# PowerPCB_mk1.net
KiCad netlist of a schematic drawn in EAGLE
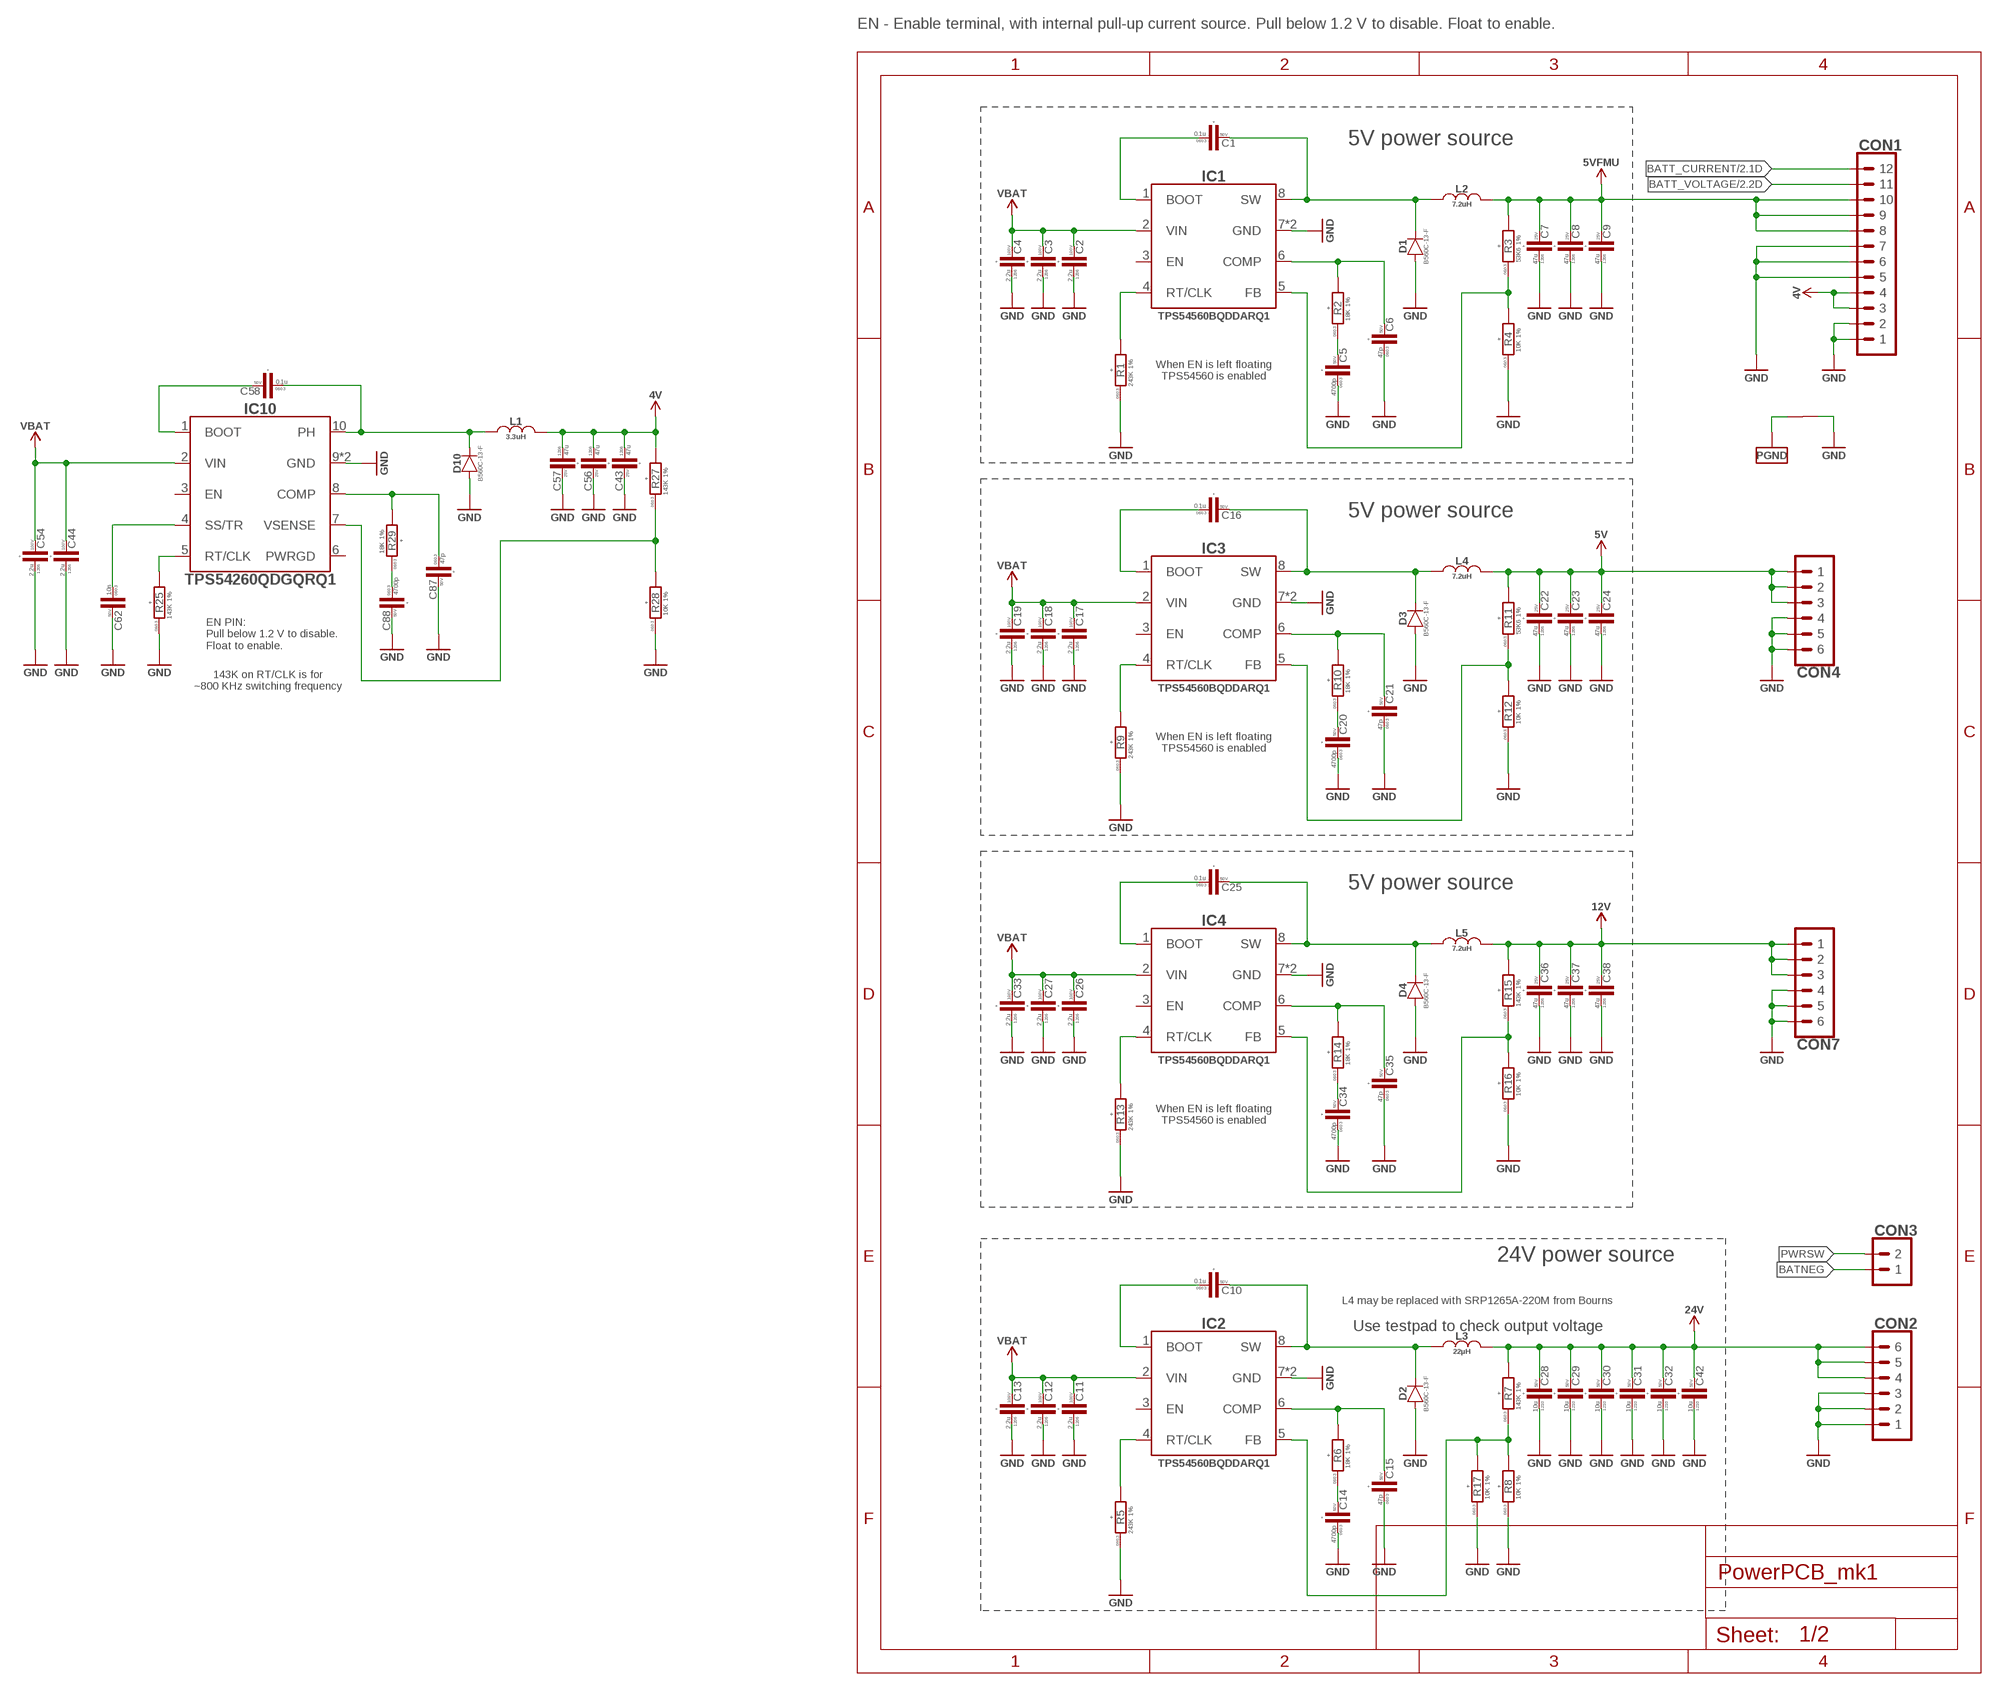
[diagram p0: schematic, sheet 1]
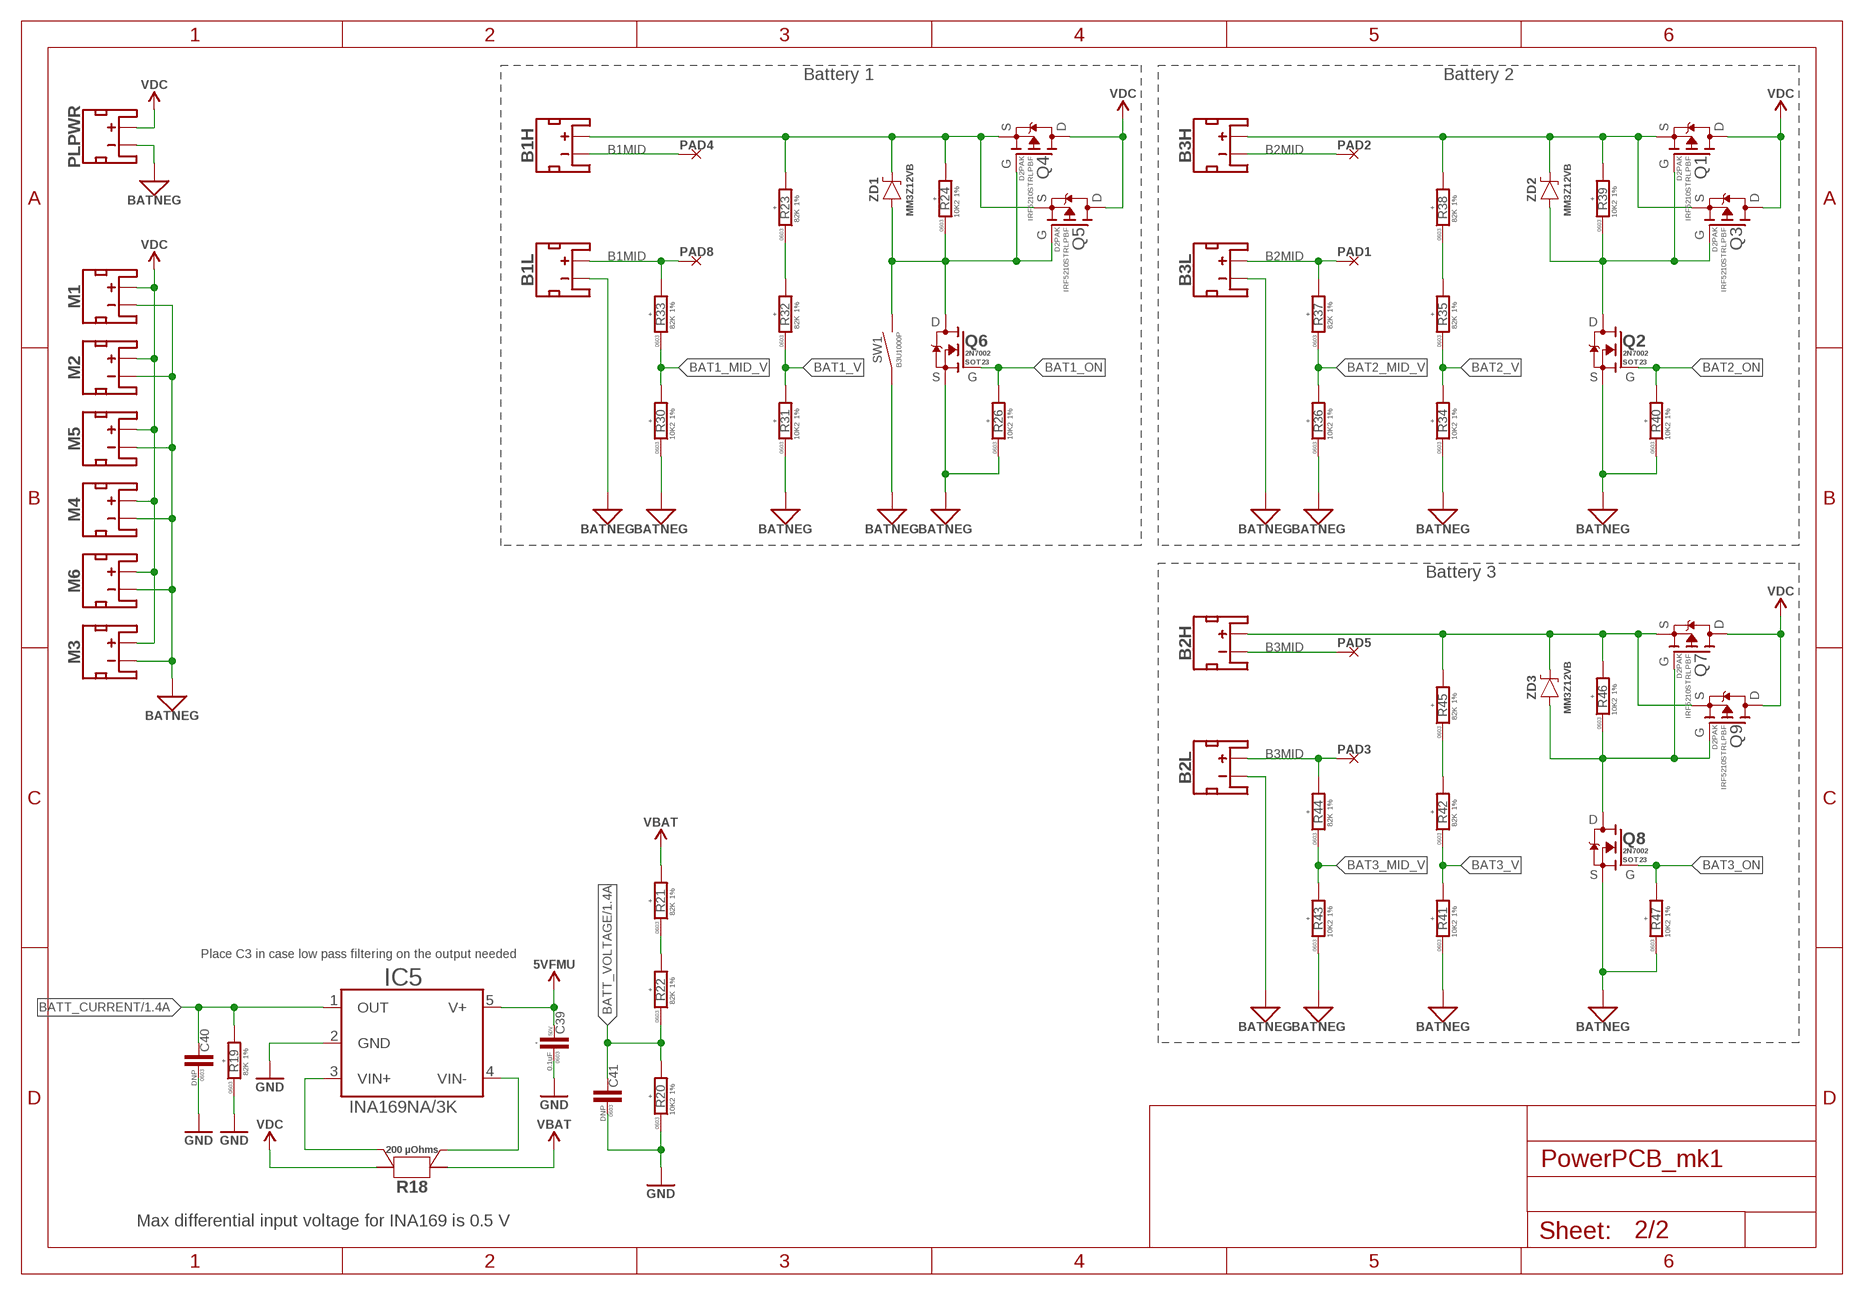
[diagram p1: schematic, sheet 2]

(export (version "E")
  (design (tool "Eeschema 10.0.6"))
  (components
    (comp (ref "B1H")
      (value "BATTERY_CON-XT60PW-M")
      (footprint "eagle-import:XT60PW-M")
      (libsource (lib "eagle-import") (part "BATTERY_CON-XT60PW-M"))
    )
    (comp (ref "B1L")
      (value "BATTERY_CON-XT60PW-M")
      (footprint "eagle-import:XT60PW-M")
      (libsource (lib "eagle-import") (part "BATTERY_CON-XT60PW-M"))
    )
    (comp (ref "B2H")
      (value "BATTERY_CON-XT60PW-M")
      (footprint "eagle-import:XT60PW-M")
      (libsource (lib "eagle-import") (part "BATTERY_CON-XT60PW-M"))
    )
    (comp (ref "B2L")
      (value "BATTERY_CON-XT60PW-M")
      (footprint "eagle-import:XT60PW-M")
      (libsource (lib "eagle-import") (part "BATTERY_CON-XT60PW-M"))
    )
    (comp (ref "B3H")
      (value "BATTERY_CON-XT60PW-M")
      (footprint "eagle-import:XT60PW-M")
      (libsource (lib "eagle-import") (part "BATTERY_CON-XT60PW-M"))
    )
    (comp (ref "B3L")
      (value "BATTERY_CON-XT60PW-M")
      (footprint "eagle-import:XT60PW-M")
      (libsource (lib "eagle-import") (part "BATTERY_CON-XT60PW-M"))
    )
    (comp (ref "C39")
      (value "0.1uF")
      (footprint "eagle-import:C0603")
      (fields
        (field (name "PACKAGE") "0603")
        (field (name "ALLOCATED") "+")
        (field (name "LCSC#") "C14663")
        (field (name "MANF") "YAGEO")
        (field (name "MANF#") "CC0603KRX7R9BB104")
        (field (name "VOLTAGE") "50V")
      )
      (libsource (lib "eagle-import") (part "C-0603"))
    )
    (comp (ref "C40")
      (value "DNP")
      (footprint "eagle-import:C0603")
      (fields (field (name "PACKAGE") "0603"))
      (libsource (lib "eagle-import") (part "C-0603"))
    )
    (comp (ref "C41")
      (value "DNP")
      (footprint "eagle-import:C0603")
      (fields (field (name "PACKAGE") "0603"))
      (libsource (lib "eagle-import") (part "C-0603"))
    )
    (comp (ref "IC5")
      (value "INA169")
      (footprint "eagle-import:SOT23-5")
      (fields (field (name "MANF") "Texas Instruments"))
      (libsource (lib "eagle-import") (part "INA169"))
    )
    (comp (ref "M1")
      (value "BATTERY_CON-XT30-RA")
      (footprint "eagle-import:XT30-RA")
      (fields (field (name "MANF") "AMASS"))
      (libsource (lib "eagle-import") (part "BATTERY_CON-XT30-RA"))
    )
    (comp (ref "M2")
      (value "BATTERY_CON-XT30-RA")
      (footprint "eagle-import:XT30-RA")
      (fields (field (name "MANF") "AMASS"))
      (libsource (lib "eagle-import") (part "BATTERY_CON-XT30-RA"))
    )
    (comp (ref "M3")
      (value "BATTERY_CON-XT30-RA")
      (footprint "eagle-import:XT30-RA")
      (fields (field (name "MANF") "AMASS"))
      (libsource (lib "eagle-import") (part "BATTERY_CON-XT30-RA"))
    )
    (comp (ref "M4")
      (value "BATTERY_CON-XT30-RA")
      (footprint "eagle-import:XT30-RA")
      (fields (field (name "MANF") "AMASS"))
      (libsource (lib "eagle-import") (part "BATTERY_CON-XT30-RA"))
    )
    (comp (ref "M5")
      (value "BATTERY_CON-XT30-RA")
      (footprint "eagle-import:XT30-RA")
      (fields (field (name "MANF") "AMASS"))
      (libsource (lib "eagle-import") (part "BATTERY_CON-XT30-RA"))
    )
    (comp (ref "M6")
      (value "BATTERY_CON-XT30-RA")
      (footprint "eagle-import:XT30-RA")
      (fields (field (name "MANF") "AMASS"))
      (libsource (lib "eagle-import") (part "BATTERY_CON-XT30-RA"))
    )
    (comp (ref "PAD1")
      (value "PAD-10X4")
      (footprint "eagle-import:10X4")
      (libsource (lib "eagle-import") (part "PAD-10X4"))
    )
    (comp (ref "PAD2")
      (value "PAD-10X4")
      (footprint "eagle-import:10X4")
      (libsource (lib "eagle-import") (part "PAD-10X4"))
    )
    (comp (ref "PAD3")
      (value "PAD-10X4")
      (footprint "eagle-import:10X4")
      (libsource (lib "eagle-import") (part "PAD-10X4"))
    )
    (comp (ref "PAD4")
      (value "PAD-10X4")
      (footprint "eagle-import:10X4")
      (libsource (lib "eagle-import") (part "PAD-10X4"))
    )
    (comp (ref "PAD5")
      (value "PAD-10X4")
      (footprint "eagle-import:10X4")
      (libsource (lib "eagle-import") (part "PAD-10X4"))
    )
    (comp (ref "PAD8")
      (value "PAD-10X4")
      (footprint "eagle-import:10X4")
      (libsource (lib "eagle-import") (part "PAD-10X4"))
    )
    (comp (ref "PLPWR")
      (value "BATTERY_CON-XT30-RA")
      (footprint "eagle-import:XT30-RA")
      (fields (field (name "MANF") "AMASS"))
      (libsource (lib "eagle-import") (part "BATTERY_CON-XT30-RA"))
    )
    (comp (ref "Q1")
      (value "IRF5210S")
      (footprint "eagle-import:D2PAK-3")
      (fields
        (field (name "MANF#") "IRF5210STRLPBF")
        (field (name "PACKAGE") "D2PAK")
        (field (name "MANF") "Infineon Technologies")
      )
      (libsource (lib "eagle-import") (part "IRF5210S"))
    )
    (comp (ref "Q2")
      (value "2N7002")
      (footprint "eagle-import:SOT23")
      (fields
        (field (name "MANF#") "2N7002")
        (field (name "PACKAGE") "SOT23")
        (field (name "MANF") "Changjiang Electronics Tech (CJ)")
      )
      (libsource (lib "eagle-import") (part "2N7002"))
    )
    (comp (ref "Q3")
      (value "IRF5210S")
      (footprint "eagle-import:D2PAK-3")
      (fields
        (field (name "MANF#") "IRF5210STRLPBF")
        (field (name "PACKAGE") "D2PAK")
        (field (name "MANF") "Infineon Technologies")
      )
      (libsource (lib "eagle-import") (part "IRF5210S"))
    )
    (comp (ref "Q4")
      (value "IRF5210S")
      (footprint "eagle-import:D2PAK-3")
      (fields
        (field (name "MANF#") "IRF5210STRLPBF")
        (field (name "PACKAGE") "D2PAK")
        (field (name "MANF") "Infineon Technologies")
      )
      (libsource (lib "eagle-import") (part "IRF5210S"))
    )
    (comp (ref "Q5")
      (value "IRF5210S")
      (footprint "eagle-import:D2PAK-3")
      (fields
        (field (name "MANF#") "IRF5210STRLPBF")
        (field (name "PACKAGE") "D2PAK")
        (field (name "MANF") "Infineon Technologies")
      )
      (libsource (lib "eagle-import") (part "IRF5210S"))
    )
    (comp (ref "Q6")
      (value "2N7002")
      (footprint "eagle-import:SOT23")
      (fields
        (field (name "MANF#") "2N7002")
        (field (name "PACKAGE") "SOT23")
        (field (name "MANF") "Changjiang Electronics Tech (CJ)")
      )
      (libsource (lib "eagle-import") (part "2N7002"))
    )
    (comp (ref "Q7")
      (value "IRF5210S")
      (footprint "eagle-import:D2PAK-3")
      (fields
        (field (name "MANF#") "IRF5210STRLPBF")
        (field (name "PACKAGE") "D2PAK")
        (field (name "MANF") "Infineon Technologies")
      )
      (libsource (lib "eagle-import") (part "IRF5210S"))
    )
    (comp (ref "Q8")
      (value "2N7002")
      (footprint "eagle-import:SOT23")
      (fields
        (field (name "MANF#") "2N7002")
        (field (name "PACKAGE") "SOT23")
        (field (name "MANF") "Changjiang Electronics Tech (CJ)")
      )
      (libsource (lib "eagle-import") (part "2N7002"))
    )
    (comp (ref "Q9")
      (value "IRF5210S")
      (footprint "eagle-import:D2PAK-3")
      (fields
        (field (name "MANF#") "IRF5210STRLPBF")
        (field (name "PACKAGE") "D2PAK")
        (field (name "MANF") "Infineon Technologies")
      )
      (libsource (lib "eagle-import") (part "IRF5210S"))
    )
    (comp (ref "R18")
      (value "200 µOhms")
      (footprint "eagle-import:R3920-KELVIN")
      (fields
        (field (name "MANF") "Bourns Inc")
        (field (name "POWER") "12W")
        (field (name "TOLERANCE") "±1%")
      )
      (libsource (lib "eagle-import") (part "CURRENT_SHUNT_KELVIN-3920-KELVIN-0.0002R"))
    )
    (comp (ref "R19")
      (value "82K")
      (footprint "eagle-import:R0603")
      (fields
        (field (name "PACKAGE") "0603")
        (field (name "TOLERANCE") "1%")
        (field (name "ALLOCATED") "+")
        (field (name "LCSC#") "C23254")
        (field (name "MANF") "UNI-ROYAL(Uniroyal Elec)")
        (field (name "MANF#") "0603WAF8202T5E")
      )
      (libsource (lib "eagle-import") (part "R-0603-1%"))
    )
    (comp (ref "R20")
      (value "10K2")
      (footprint "eagle-import:R0603")
      (fields
        (field (name "PACKAGE") "0603")
        (field (name "TOLERANCE") "1%")
        (field (name "ALLOCATED") "+")
        (field (name "LCSC#") "C22772")
        (field (name "MANF") "UNI-ROYAL(Uniroyal Elec)")
        (field (name "MANF#") "0603WAF1022T5E")
      )
      (libsource (lib "eagle-import") (part "R-0603-1%"))
    )
    (comp (ref "R21")
      (value "82K")
      (footprint "eagle-import:R0603")
      (fields
        (field (name "PACKAGE") "0603")
        (field (name "TOLERANCE") "1%")
        (field (name "ALLOCATED") "+")
        (field (name "LCSC#") "C23254")
        (field (name "MANF") "UNI-ROYAL(Uniroyal Elec)")
        (field (name "MANF#") "0603WAF8202T5E")
      )
      (libsource (lib "eagle-import") (part "R-0603-1%"))
    )
    (comp (ref "R22")
      (value "82K")
      (footprint "eagle-import:R0603")
      (fields
        (field (name "PACKAGE") "0603")
        (field (name "TOLERANCE") "1%")
        (field (name "ALLOCATED") "+")
        (field (name "LCSC#") "C23254")
        (field (name "MANF") "UNI-ROYAL(Uniroyal Elec)")
        (field (name "MANF#") "0603WAF8202T5E")
      )
      (libsource (lib "eagle-import") (part "R-0603-1%"))
    )
    (comp (ref "R23")
      (value "82K")
      (footprint "eagle-import:R0603")
      (fields
        (field (name "PACKAGE") "0603")
        (field (name "TOLERANCE") "1%")
        (field (name "ALLOCATED") "+")
        (field (name "LCSC#") "C23254")
        (field (name "MANF") "UNI-ROYAL(Uniroyal Elec)")
        (field (name "MANF#") "0603WAF8202T5E")
      )
      (libsource (lib "eagle-import") (part "R-0603-1%"))
    )
    (comp (ref "R24")
      (value "10K2")
      (footprint "eagle-import:R0603")
      (fields
        (field (name "PACKAGE") "0603")
        (field (name "TOLERANCE") "1%")
        (field (name "ALLOCATED") "+")
        (field (name "LCSC#") "C22772")
        (field (name "MANF") "UNI-ROYAL(Uniroyal Elec)")
        (field (name "MANF#") "0603WAF1022T5E")
      )
      (libsource (lib "eagle-import") (part "R-0603-1%"))
    )
    (comp (ref "R26")
      (value "10K2")
      (footprint "eagle-import:R0603")
      (fields
        (field (name "PACKAGE") "0603")
        (field (name "TOLERANCE") "1%")
        (field (name "ALLOCATED") "+")
        (field (name "LCSC#") "C22772")
        (field (name "MANF") "UNI-ROYAL(Uniroyal Elec)")
        (field (name "MANF#") "0603WAF1022T5E")
      )
      (libsource (lib "eagle-import") (part "R-0603-1%"))
    )
    (comp (ref "R30")
      (value "10K2")
      (footprint "eagle-import:R0603")
      (fields
        (field (name "PACKAGE") "0603")
        (field (name "TOLERANCE") "1%")
        (field (name "ALLOCATED") "+")
        (field (name "LCSC#") "C22772")
        (field (name "MANF") "UNI-ROYAL(Uniroyal Elec)")
        (field (name "MANF#") "0603WAF1022T5E")
      )
      (libsource (lib "eagle-import") (part "R-0603-1%"))
    )
    (comp (ref "R31")
      (value "10K2")
      (footprint "eagle-import:R0603")
      (fields
        (field (name "PACKAGE") "0603")
        (field (name "TOLERANCE") "1%")
        (field (name "ALLOCATED") "+")
        (field (name "LCSC#") "C22772")
        (field (name "MANF") "UNI-ROYAL(Uniroyal Elec)")
        (field (name "MANF#") "0603WAF1022T5E")
      )
      (libsource (lib "eagle-import") (part "R-0603-1%"))
    )
    (comp (ref "R32")
      (value "82K")
      (footprint "eagle-import:R0603")
      (fields
        (field (name "PACKAGE") "0603")
        (field (name "TOLERANCE") "1%")
        (field (name "ALLOCATED") "+")
        (field (name "LCSC#") "C23254")
        (field (name "MANF") "UNI-ROYAL(Uniroyal Elec)")
        (field (name "MANF#") "0603WAF8202T5E")
      )
      (libsource (lib "eagle-import") (part "R-0603-1%"))
    )
    (comp (ref "R33")
      (value "82K")
      (footprint "eagle-import:R0603")
      (fields
        (field (name "PACKAGE") "0603")
        (field (name "TOLERANCE") "1%")
        (field (name "ALLOCATED") "+")
        (field (name "LCSC#") "C23254")
        (field (name "MANF") "UNI-ROYAL(Uniroyal Elec)")
        (field (name "MANF#") "0603WAF8202T5E")
      )
      (libsource (lib "eagle-import") (part "R-0603-1%"))
    )
    (comp (ref "R34")
      (value "10K2")
      (footprint "eagle-import:R0603")
      (fields
        (field (name "PACKAGE") "0603")
        (field (name "TOLERANCE") "1%")
        (field (name "ALLOCATED") "+")
        (field (name "LCSC#") "C22772")
        (field (name "MANF") "UNI-ROYAL(Uniroyal Elec)")
        (field (name "MANF#") "0603WAF1022T5E")
      )
      (libsource (lib "eagle-import") (part "R-0603-1%"))
    )
    (comp (ref "R35")
      (value "82K")
      (footprint "eagle-import:R0603")
      (fields
        (field (name "PACKAGE") "0603")
        (field (name "TOLERANCE") "1%")
        (field (name "ALLOCATED") "+")
        (field (name "LCSC#") "C23254")
        (field (name "MANF") "UNI-ROYAL(Uniroyal Elec)")
        (field (name "MANF#") "0603WAF8202T5E")
      )
      (libsource (lib "eagle-import") (part "R-0603-1%"))
    )
    (comp (ref "R36")
      (value "10K2")
      (footprint "eagle-import:R0603")
      (fields
        (field (name "PACKAGE") "0603")
        (field (name "TOLERANCE") "1%")
        (field (name "ALLOCATED") "+")
        (field (name "LCSC#") "C22772")
        (field (name "MANF") "UNI-ROYAL(Uniroyal Elec)")
        (field (name "MANF#") "0603WAF1022T5E")
      )
      (libsource (lib "eagle-import") (part "R-0603-1%"))
    )
    (comp (ref "R37")
      (value "82K")
      (footprint "eagle-import:R0603")
      (fields
        (field (name "PACKAGE") "0603")
        (field (name "TOLERANCE") "1%")
        (field (name "ALLOCATED") "+")
        (field (name "LCSC#") "C23254")
        (field (name "MANF") "UNI-ROYAL(Uniroyal Elec)")
        (field (name "MANF#") "0603WAF8202T5E")
      )
      (libsource (lib "eagle-import") (part "R-0603-1%"))
    )
    (comp (ref "R38")
      (value "82K")
      (footprint "eagle-import:R0603")
      (fields
        (field (name "PACKAGE") "0603")
        (field (name "TOLERANCE") "1%")
        (field (name "ALLOCATED") "+")
        (field (name "LCSC#") "C23254")
        (field (name "MANF") "UNI-ROYAL(Uniroyal Elec)")
        (field (name "MANF#") "0603WAF8202T5E")
      )
      (libsource (lib "eagle-import") (part "R-0603-1%"))
    )
    (comp (ref "R39")
      (value "10K2")
      (footprint "eagle-import:R0603")
      (fields
        (field (name "PACKAGE") "0603")
        (field (name "TOLERANCE") "1%")
        (field (name "ALLOCATED") "+")
        (field (name "LCSC#") "C22772")
        (field (name "MANF") "UNI-ROYAL(Uniroyal Elec)")
        (field (name "MANF#") "0603WAF1022T5E")
      )
      (libsource (lib "eagle-import") (part "R-0603-1%"))
    )
    (comp (ref "R40")
      (value "10K2")
      (footprint "eagle-import:R0603")
      (fields
        (field (name "PACKAGE") "0603")
        (field (name "TOLERANCE") "1%")
        (field (name "ALLOCATED") "+")
        (field (name "LCSC#") "C22772")
        (field (name "MANF") "UNI-ROYAL(Uniroyal Elec)")
        (field (name "MANF#") "0603WAF1022T5E")
      )
      (libsource (lib "eagle-import") (part "R-0603-1%"))
    )
    (comp (ref "R41")
      (value "10K2")
      (footprint "eagle-import:R0603")
      (fields
        (field (name "PACKAGE") "0603")
        (field (name "TOLERANCE") "1%")
        (field (name "ALLOCATED") "+")
        (field (name "LCSC#") "C22772")
        (field (name "MANF") "UNI-ROYAL(Uniroyal Elec)")
        (field (name "MANF#") "0603WAF1022T5E")
      )
      (libsource (lib "eagle-import") (part "R-0603-1%"))
    )
    (comp (ref "R42")
      (value "82K")
      (footprint "eagle-import:R0603")
      (fields
        (field (name "PACKAGE") "0603")
        (field (name "TOLERANCE") "1%")
        (field (name "ALLOCATED") "+")
        (field (name "LCSC#") "C23254")
        (field (name "MANF") "UNI-ROYAL(Uniroyal Elec)")
        (field (name "MANF#") "0603WAF8202T5E")
      )
      (libsource (lib "eagle-import") (part "R-0603-1%"))
    )
    (comp (ref "R43")
      (value "10K2")
      (footprint "eagle-import:R0603")
      (fields
        (field (name "PACKAGE") "0603")
        (field (name "TOLERANCE") "1%")
        (field (name "ALLOCATED") "+")
        (field (name "LCSC#") "C22772")
        (field (name "MANF") "UNI-ROYAL(Uniroyal Elec)")
        (field (name "MANF#") "0603WAF1022T5E")
      )
      (libsource (lib "eagle-import") (part "R-0603-1%"))
    )
    (comp (ref "R44")
      (value "82K")
      (footprint "eagle-import:R0603")
      (fields
        (field (name "PACKAGE") "0603")
        (field (name "TOLERANCE") "1%")
        (field (name "ALLOCATED") "+")
        (field (name "LCSC#") "C23254")
        (field (name "MANF") "UNI-ROYAL(Uniroyal Elec)")
        (field (name "MANF#") "0603WAF8202T5E")
      )
      (libsource (lib "eagle-import") (part "R-0603-1%"))
    )
    (comp (ref "R45")
      (value "82K")
      (footprint "eagle-import:R0603")
      (fields
        (field (name "PACKAGE") "0603")
        (field (name "TOLERANCE") "1%")
        (field (name "ALLOCATED") "+")
        (field (name "LCSC#") "C23254")
        (field (name "MANF") "UNI-ROYAL(Uniroyal Elec)")
        (field (name "MANF#") "0603WAF8202T5E")
      )
      (libsource (lib "eagle-import") (part "R-0603-1%"))
    )
    (comp (ref "R46")
      (value "10K2")
      (footprint "eagle-import:R0603")
      (fields
        (field (name "PACKAGE") "0603")
        (field (name "TOLERANCE") "1%")
        (field (name "ALLOCATED") "+")
        (field (name "LCSC#") "C22772")
        (field (name "MANF") "UNI-ROYAL(Uniroyal Elec)")
        (field (name "MANF#") "0603WAF1022T5E")
      )
      (libsource (lib "eagle-import") (part "R-0603-1%"))
    )
    (comp (ref "R47")
      (value "10K2")
      (footprint "eagle-import:R0603")
      (fields
        (field (name "PACKAGE") "0603")
        (field (name "TOLERANCE") "1%")
        (field (name "ALLOCATED") "+")
        (field (name "LCSC#") "C22772")
        (field (name "MANF") "UNI-ROYAL(Uniroyal Elec)")
        (field (name "MANF#") "0603WAF1022T5E")
      )
      (libsource (lib "eagle-import") (part "R-0603-1%"))
    )
    (comp (ref "SW1")
      (value "TACT_SWITCH-B3U1000P")
      (footprint "eagle-import:B3U1000P")
      (fields (field (name "MANF") "OMRON"))
      (libsource (lib "eagle-import") (part "TACT_SWITCH-B3U1000P"))
    )
    (comp (ref "ZD1")
      (value "MM3Z12V")
      (footprint "eagle-import:SOD323")
      (fields (field (name "MANF") "onsemi") (field (name "MANF#") "MM3Z12VB"))
      (libsource (lib "eagle-import") (part "MM3Z12V"))
    )
    (comp (ref "ZD2")
      (value "MM3Z12V")
      (footprint "eagle-import:SOD323")
      (fields (field (name "MANF") "onsemi") (field (name "MANF#") "MM3Z12VB"))
      (libsource (lib "eagle-import") (part "MM3Z12V"))
    )
    (comp (ref "ZD3")
      (value "MM3Z12V")
      (footprint "eagle-import:SOD323")
      (fields (field (name "MANF") "onsemi") (field (name "MANF#") "MM3Z12VB"))
      (libsource (lib "eagle-import") (part "MM3Z12V"))
    )
    (comp (ref "C1")
      (value "0.1u")
      (footprint "eagle-import:C0603")
      (fields
        (field (name "PACKAGE") "0603")
        (field (name "ALLOCATED") "+")
        (field (name "LCSC#") "C14663")
        (field (name "MANF") "YAGEO")
        (field (name "MANF#") "CC0603KRX7R9BB104")
        (field (name "VOLTAGE") "50V")
      )
      (libsource (lib "eagle-import") (part "C-0603"))
    )
    (comp (ref "C2")
      (value "2.2u")
      (footprint "eagle-import:C1206")
      (fields
        (field (name "PACKAGE") "1206")
        (field (name "ALLOCATED") "+")
        (field (name "LCSC#") "C170101")
        (field (name "MANF") "Samsung Electro-Mechanics")
        (field (name "MANF#") "CL31B225KCHSNNE")
        (field (name "VOLTAGE") "100V")
      )
      (libsource (lib "eagle-import") (part "C-1206"))
    )
    (comp (ref "C3")
      (value "2.2u")
      (footprint "eagle-import:C1206")
      (fields
        (field (name "PACKAGE") "1206")
        (field (name "ALLOCATED") "+")
        (field (name "LCSC#") "C170101")
        (field (name "MANF") "Samsung Electro-Mechanics")
        (field (name "MANF#") "CL31B225KCHSNNE")
        (field (name "VOLTAGE") "100V")
      )
      (libsource (lib "eagle-import") (part "C-1206"))
    )
    (comp (ref "C4")
      (value "2.2u")
      (footprint "eagle-import:C1206")
      (fields
        (field (name "PACKAGE") "1206")
        (field (name "ALLOCATED") "+")
        (field (name "LCSC#") "C170101")
        (field (name "MANF") "Samsung Electro-Mechanics")
        (field (name "MANF#") "CL31B225KCHSNNE")
        (field (name "VOLTAGE") "100V")
      )
      (libsource (lib "eagle-import") (part "C-1206"))
    )
    (comp (ref "C5")
      (value "4700p")
      (footprint "eagle-import:C0603")
      (fields
        (field (name "PACKAGE") "0603")
        (field (name "ALLOCATED") "+")
        (field (name "LCSC#") "C106218")
        (field (name "MANF") "YAGEO")
        (field (name "MANF#") "CC0603KRX7R9BB472")
        (field (name "VOLTAGE") "50V")
      )
      (libsource (lib "eagle-import") (part "C-0603"))
    )
    (comp (ref "C6")
      (value "47p")
      (footprint "eagle-import:C0603")
      (fields
        (field (name "PACKAGE") "0603")
        (field (name "ALLOCATED") "+")
        (field (name "LCSC#") "C1671")
        (field (name "MANF") "Samsung Electro-Mechanics")
        (field (name "MANF#") "CL10C470JB8NNNC")
        (field (name "VOLTAGE") "50V")
      )
      (libsource (lib "eagle-import") (part "C-0603"))
    )
    (comp (ref "C7")
      (value "47u")
      (footprint "eagle-import:C1206")
      (fields
        (field (name "PACKAGE") "1206")
        (field (name "ALLOCATED") "+")
        (field (name "LCSC#") "C403725")
        (field (name "MANF") "Murata Electronics")
        (field (name "MANF#") "GRM31CR61E476ME44L")
        (field (name "VOLTAGE") "25V")
      )
      (libsource (lib "eagle-import") (part "C-1206"))
    )
    (comp (ref "C8")
      (value "47u")
      (footprint "eagle-import:C1206")
      (fields
        (field (name "PACKAGE") "1206")
        (field (name "ALLOCATED") "+")
        (field (name "LCSC#") "C403725")
        (field (name "MANF") "Murata Electronics")
        (field (name "MANF#") "GRM31CR61E476ME44L")
        (field (name "VOLTAGE") "25V")
      )
      (libsource (lib "eagle-import") (part "C-1206"))
    )
    (comp (ref "C9")
      (value "47u")
      (footprint "eagle-import:C1206")
      (fields
        (field (name "PACKAGE") "1206")
        (field (name "ALLOCATED") "+")
        (field (name "LCSC#") "C403725")
        (field (name "MANF") "Murata Electronics")
        (field (name "MANF#") "GRM31CR61E476ME44L")
        (field (name "VOLTAGE") "25V")
      )
      (libsource (lib "eagle-import") (part "C-1206"))
    )
    (comp (ref "C10")
      (value "0.1u")
      (footprint "eagle-import:C0603")
      (fields
        (field (name "PACKAGE") "0603")
        (field (name "ALLOCATED") "+")
        (field (name "LCSC#") "C14663")
        (field (name "MANF") "YAGEO")
        (field (name "MANF#") "CC0603KRX7R9BB104")
        (field (name "VOLTAGE") "50V")
      )
      (libsource (lib "eagle-import") (part "C-0603"))
    )
    (comp (ref "C11")
      (value "2.2u")
      (footprint "eagle-import:C1206")
      (fields
        (field (name "PACKAGE") "1206")
        (field (name "ALLOCATED") "+")
        (field (name "LCSC#") "C170101")
        (field (name "MANF") "Samsung Electro-Mechanics")
        (field (name "MANF#") "CL31B225KCHSNNE")
        (field (name "VOLTAGE") "100V")
      )
      (libsource (lib "eagle-import") (part "C-1206"))
    )
    (comp (ref "C12")
      (value "2.2u")
      (footprint "eagle-import:C1206")
      (fields
        (field (name "PACKAGE") "1206")
        (field (name "ALLOCATED") "+")
        (field (name "LCSC#") "C170101")
        (field (name "MANF") "Samsung Electro-Mechanics")
        (field (name "MANF#") "CL31B225KCHSNNE")
        (field (name "VOLTAGE") "100V")
      )
      (libsource (lib "eagle-import") (part "C-1206"))
    )
    (comp (ref "C13")
      (value "2.2u")
      (footprint "eagle-import:C1206")
      (fields
        (field (name "PACKAGE") "1206")
        (field (name "ALLOCATED") "+")
        (field (name "LCSC#") "C170101")
        (field (name "MANF") "Samsung Electro-Mechanics")
        (field (name "MANF#") "CL31B225KCHSNNE")
        (field (name "VOLTAGE") "100V")
      )
      (libsource (lib "eagle-import") (part "C-1206"))
    )
    (comp (ref "C14")
      (value "4700p")
      (footprint "eagle-import:C0603")
      (fields
        (field (name "PACKAGE") "0603")
        (field (name "ALLOCATED") "+")
        (field (name "LCSC#") "C106218")
        (field (name "MANF") "YAGEO")
        (field (name "MANF#") "CC0603KRX7R9BB472")
        (field (name "VOLTAGE") "50V")
      )
      (libsource (lib "eagle-import") (part "C-0603"))
    )
    (comp (ref "C15")
      (value "47p")
      (footprint "eagle-import:C0603")
      (fields
        (field (name "PACKAGE") "0603")
        (field (name "ALLOCATED") "+")
        (field (name "LCSC#") "C1671")
        (field (name "MANF") "Samsung Electro-Mechanics")
        (field (name "MANF#") "CL10C470JB8NNNC")
        (field (name "VOLTAGE") "50V")
      )
      (libsource (lib "eagle-import") (part "C-0603"))
    )
    (comp (ref "C16")
      (value "0.1u")
      (footprint "eagle-import:C0603")
      (fields
        (field (name "PACKAGE") "0603")
        (field (name "ALLOCATED") "+")
        (field (name "LCSC#") "C14663")
        (field (name "MANF") "YAGEO")
        (field (name "MANF#") "CC0603KRX7R9BB104")
        (field (name "VOLTAGE") "50V")
      )
      (libsource (lib "eagle-import") (part "C-0603"))
    )
    (comp (ref "C17")
      (value "2.2u")
      (footprint "eagle-import:C1206")
      (fields
        (field (name "PACKAGE") "1206")
        (field (name "ALLOCATED") "+")
        (field (name "LCSC#") "C170101")
        (field (name "MANF") "Samsung Electro-Mechanics")
        (field (name "MANF#") "CL31B225KCHSNNE")
        (field (name "VOLTAGE") "100V")
      )
      (libsource (lib "eagle-import") (part "C-1206"))
    )
    (comp (ref "C18")
      (value "2.2u")
      (footprint "eagle-import:C1206")
      (fields
        (field (name "PACKAGE") "1206")
        (field (name "ALLOCATED") "+")
        (field (name "LCSC#") "C170101")
        (field (name "MANF") "Samsung Electro-Mechanics")
        (field (name "MANF#") "CL31B225KCHSNNE")
        (field (name "VOLTAGE") "100V")
      )
      (libsource (lib "eagle-import") (part "C-1206"))
    )
    (comp (ref "C19")
      (value "2.2u")
      (footprint "eagle-import:C1206")
      (fields
        (field (name "PACKAGE") "1206")
        (field (name "ALLOCATED") "+")
        (field (name "LCSC#") "C170101")
        (field (name "MANF") "Samsung Electro-Mechanics")
        (field (name "MANF#") "CL31B225KCHSNNE")
        (field (name "VOLTAGE") "100V")
      )
      (libsource (lib "eagle-import") (part "C-1206"))
    )
    (comp (ref "C20")
      (value "4700p")
      (footprint "eagle-import:C0603")
      (fields
        (field (name "PACKAGE") "0603")
        (field (name "ALLOCATED") "+")
        (field (name "LCSC#") "C106218")
        (field (name "MANF") "YAGEO")
        (field (name "MANF#") "CC0603KRX7R9BB472")
        (field (name "VOLTAGE") "50V")
      )
      (libsource (lib "eagle-import") (part "C-0603"))
    )
    (comp (ref "C21")
      (value "47p")
      (footprint "eagle-import:C0603")
      (fields
        (field (name "PACKAGE") "0603")
        (field (name "ALLOCATED") "+")
        (field (name "LCSC#") "C1671")
        (field (name "MANF") "Samsung Electro-Mechanics")
        (field (name "MANF#") "CL10C470JB8NNNC")
        (field (name "VOLTAGE") "50V")
      )
      (libsource (lib "eagle-import") (part "C-0603"))
    )
    (comp (ref "C22")
      (value "47u")
      (footprint "eagle-import:C1206")
      (fields
        (field (name "PACKAGE") "1206")
        (field (name "ALLOCATED") "+")
        (field (name "LCSC#") "C403725")
        (field (name "MANF") "Murata Electronics")
        (field (name "MANF#") "GRM31CR61E476ME44L")
        (field (name "VOLTAGE") "25V")
      )
      (libsource (lib "eagle-import") (part "C-1206"))
    )
    (comp (ref "C23")
      (value "47u")
      (footprint "eagle-import:C1206")
      (fields
        (field (name "PACKAGE") "1206")
        (field (name "ALLOCATED") "+")
        (field (name "LCSC#") "C403725")
        (field (name "MANF") "Murata Electronics")
        (field (name "MANF#") "GRM31CR61E476ME44L")
        (field (name "VOLTAGE") "25V")
      )
      (libsource (lib "eagle-import") (part "C-1206"))
    )
    (comp (ref "C24")
      (value "47u")
      (footprint "eagle-import:C1206")
      (fields
        (field (name "PACKAGE") "1206")
        (field (name "ALLOCATED") "+")
        (field (name "LCSC#") "C403725")
        (field (name "MANF") "Murata Electronics")
        (field (name "MANF#") "GRM31CR61E476ME44L")
        (field (name "VOLTAGE") "25V")
      )
      (libsource (lib "eagle-import") (part "C-1206"))
    )
    (comp (ref "C25")
      (value "0.1u")
      (footprint "eagle-import:C0603")
      (fields
        (field (name "PACKAGE") "0603")
        (field (name "ALLOCATED") "+")
        (field (name "LCSC#") "C14663")
        (field (name "MANF") "YAGEO")
        (field (name "MANF#") "CC0603KRX7R9BB104")
        (field (name "VOLTAGE") "50V")
      )
      (libsource (lib "eagle-import") (part "C-0603"))
    )
    (comp (ref "C26")
      (value "2.2u")
      (footprint "eagle-import:C1206")
      (fields
        (field (name "PACKAGE") "1206")
        (field (name "ALLOCATED") "+")
        (field (name "LCSC#") "C170101")
        (field (name "MANF") "Samsung Electro-Mechanics")
        (field (name "MANF#") "CL31B225KCHSNNE")
        (field (name "VOLTAGE") "100V")
      )
      (libsource (lib "eagle-import") (part "C-1206"))
    )
    (comp (ref "C27")
      (value "2.2u")
      (footprint "eagle-import:C1206")
      (fields
        (field (name "PACKAGE") "1206")
        (field (name "ALLOCATED") "+")
        (field (name "LCSC#") "C170101")
        (field (name "MANF") "Samsung Electro-Mechanics")
        (field (name "MANF#") "CL31B225KCHSNNE")
        (field (name "VOLTAGE") "100V")
      )
      (libsource (lib "eagle-import") (part "C-1206"))
    )
    (comp (ref "C28")
      (value "10u")
      (footprint "eagle-import:C1210")
      (fields
        (field (name "PACKAGE") "1210")
        (field (name "ALLOCATED") "+")
        (field (name "LCSC#") "C77102")
        (field (name "MANF") "Murata Electronics")
        (field (name "MANF#") "GRM32ER71H106K")
        (field (name "VOLTAGE") "50V")
      )
      (libsource (lib "eagle-import") (part "C-1210"))
    )
    (comp (ref "C29")
      (value "10u")
      (footprint "eagle-import:C1210")
      (fields
        (field (name "PACKAGE") "1210")
        (field (name "ALLOCATED") "+")
        (field (name "LCSC#") "C77102")
        (field (name "MANF") "Murata Electronics")
        (field (name "MANF#") "GRM32ER71H106K")
        (field (name "VOLTAGE") "50V")
      )
      (libsource (lib "eagle-import") (part "C-1210"))
    )
    (comp (ref "C30")
      (value "10u")
      (footprint "eagle-import:C1210")
      (fields
        (field (name "PACKAGE") "1210")
        (field (name "ALLOCATED") "+")
        (field (name "LCSC#") "C77102")
        (field (name "MANF") "Murata Electronics")
        (field (name "MANF#") "GRM32ER71H106K")
        (field (name "VOLTAGE") "50V")
      )
      (libsource (lib "eagle-import") (part "C-1210"))
    )
    (comp (ref "C31")
      (value "10u")
      (footprint "eagle-import:C1210")
      (fields
        (field (name "PACKAGE") "1210")
        (field (name "ALLOCATED") "+")
        (field (name "LCSC#") "C77102")
        (field (name "MANF") "Murata Electronics")
        (field (name "MANF#") "GRM32ER71H106K")
        (field (name "VOLTAGE") "50V")
      )
      (libsource (lib "eagle-import") (part "C-1210"))
    )
    (comp (ref "C32")
      (value "10u")
      (footprint "eagle-import:C1210")
      (fields
        (field (name "PACKAGE") "1210")
        (field (name "ALLOCATED") "+")
        (field (name "LCSC#") "C77102")
        (field (name "MANF") "Murata Electronics")
        (field (name "MANF#") "GRM32ER71H106K")
        (field (name "VOLTAGE") "50V")
      )
      (libsource (lib "eagle-import") (part "C-1210"))
    )
    (comp (ref "C33")
      (value "2.2u")
      (footprint "eagle-import:C1206")
      (fields
        (field (name "PACKAGE") "1206")
        (field (name "ALLOCATED") "+")
        (field (name "LCSC#") "C170101")
        (field (name "MANF") "Samsung Electro-Mechanics")
        (field (name "MANF#") "CL31B225KCHSNNE")
        (field (name "VOLTAGE") "100V")
      )
      (libsource (lib "eagle-import") (part "C-1206"))
    )
    (comp (ref "C34")
      (value "4700p")
      (footprint "eagle-import:C0603")
      (fields
        (field (name "PACKAGE") "0603")
        (field (name "ALLOCATED") "+")
        (field (name "LCSC#") "C106218")
        (field (name "MANF") "YAGEO")
        (field (name "MANF#") "CC0603KRX7R9BB472")
        (field (name "VOLTAGE") "50V")
      )
      (libsource (lib "eagle-import") (part "C-0603"))
    )
    (comp (ref "C35")
      (value "47p")
      (footprint "eagle-import:C0603")
      (fields
        (field (name "PACKAGE") "0603")
        (field (name "ALLOCATED") "+")
        (field (name "LCSC#") "C1671")
        (field (name "MANF") "Samsung Electro-Mechanics")
        (field (name "MANF#") "CL10C470JB8NNNC")
        (field (name "VOLTAGE") "50V")
      )
      (libsource (lib "eagle-import") (part "C-0603"))
    )
    (comp (ref "C36")
      (value "47u")
      (footprint "eagle-import:C1206")
      (fields
        (field (name "PACKAGE") "1206")
        (field (name "ALLOCATED") "+")
        (field (name "LCSC#") "C403725")
        (field (name "MANF") "Murata Electronics")
        (field (name "MANF#") "GRM31CR61E476ME44L")
        (field (name "VOLTAGE") "25V")
      )
      (libsource (lib "eagle-import") (part "C-1206"))
    )
    (comp (ref "C37")
      (value "47u")
      (footprint "eagle-import:C1206")
      (fields
        (field (name "PACKAGE") "1206")
        (field (name "ALLOCATED") "+")
        (field (name "LCSC#") "C403725")
        (field (name "MANF") "Murata Electronics")
        (field (name "MANF#") "GRM31CR61E476ME44L")
        (field (name "VOLTAGE") "25V")
      )
      (libsource (lib "eagle-import") (part "C-1206"))
    )
    (comp (ref "C38")
      (value "47u")
      (footprint "eagle-import:C1206")
      (fields
        (field (name "PACKAGE") "1206")
        (field (name "ALLOCATED") "+")
        (field (name "LCSC#") "C403725")
        (field (name "MANF") "Murata Electronics")
        (field (name "MANF#") "GRM31CR61E476ME44L")
        (field (name "VOLTAGE") "25V")
      )
      (libsource (lib "eagle-import") (part "C-1206"))
    )
    (comp (ref "C42")
      (value "10u")
      (footprint "eagle-import:C1210")
      (fields
        (field (name "PACKAGE") "1210")
        (field (name "ALLOCATED") "+")
        (field (name "LCSC#") "C77102")
        (field (name "MANF") "Murata Electronics")
        (field (name "MANF#") "GRM32ER71H106K")
        (field (name "VOLTAGE") "50V")
      )
      (libsource (lib "eagle-import") (part "C-1210"))
    )
    (comp (ref "C43")
      (value "47u")
      (footprint "eagle-import:C1206")
      (fields
        (field (name "PACKAGE") "1206")
        (field (name "ALLOCATED") "+")
        (field (name "LCSC#") "C403725")
        (field (name "MANF") "Murata Electronics")
        (field (name "MANF#") "GRM31CR61E476ME44L")
        (field (name "VOLTAGE") "25V")
      )
      (libsource (lib "eagle-import") (part "C-1206"))
    )
    (comp (ref "C44")
      (value "2.2u")
      (footprint "eagle-import:C1206")
      (fields
        (field (name "PACKAGE") "1206")
        (field (name "ALLOCATED") "+")
        (field (name "LCSC#") "C170101")
        (field (name "MANF") "Samsung Electro-Mechanics")
        (field (name "MANF#") "CL31B225KCHSNNE")
        (field (name "VOLTAGE") "100V")
      )
      (libsource (lib "eagle-import") (part "C-1206"))
    )
    (comp (ref "C54")
      (value "2.2u")
      (footprint "eagle-import:C1206")
      (fields
        (field (name "PACKAGE") "1206")
        (field (name "ALLOCATED") "+")
        (field (name "LCSC#") "C170101")
        (field (name "MANF") "Samsung Electro-Mechanics")
        (field (name "MANF#") "CL31B225KCHSNNE")
        (field (name "VOLTAGE") "100V")
      )
      (libsource (lib "eagle-import") (part "C-1206"))
    )
    (comp (ref "C56")
      (value "47u")
      (footprint "eagle-import:C1206")
      (fields
        (field (name "PACKAGE") "1206")
        (field (name "ALLOCATED") "+")
        (field (name "LCSC#") "C403725")
        (field (name "MANF") "Murata Electronics")
        (field (name "MANF#") "GRM31CR61E476ME44L")
        (field (name "VOLTAGE") "25V")
      )
      (libsource (lib "eagle-import") (part "C-1206"))
    )
    (comp (ref "C57")
      (value "47u")
      (footprint "eagle-import:C1206")
      (fields
        (field (name "PACKAGE") "1206")
        (field (name "ALLOCATED") "+")
        (field (name "LCSC#") "C403725")
        (field (name "MANF") "Murata Electronics")
        (field (name "MANF#") "GRM31CR61E476ME44L")
        (field (name "VOLTAGE") "25V")
      )
      (libsource (lib "eagle-import") (part "C-1206"))
    )
    (comp (ref "C58")
      (value "0.1u")
      (footprint "eagle-import:C0603")
      (fields
        (field (name "PACKAGE") "0603")
        (field (name "ALLOCATED") "+")
        (field (name "LCSC#") "C14663")
        (field (name "MANF") "YAGEO")
        (field (name "MANF#") "CC0603KRX7R9BB104")
        (field (name "VOLTAGE") "50V")
      )
      (libsource (lib "eagle-import") (part "C-0603"))
    )
    (comp (ref "C62")
      (value "10n")
      (footprint "eagle-import:C0603")
      (fields (field (name "PACKAGE") "0603") (field (name "VOLTAGE") "50V"))
      (libsource (lib "eagle-import") (part "C-0603"))
    )
    (comp (ref "C87")
      (value "47p")
      (footprint "eagle-import:C0603")
      (fields
        (field (name "PACKAGE") "0603")
        (field (name "ALLOCATED") "+")
        (field (name "LCSC#") "C1671")
        (field (name "MANF") "Samsung Electro-Mechanics")
        (field (name "MANF#") "CL10C470JB8NNNC")
        (field (name "VOLTAGE") "50V")
      )
      (libsource (lib "eagle-import") (part "C-0603"))
    )
    (comp (ref "C88")
      (value "4700p")
      (footprint "eagle-import:C0603")
      (fields
        (field (name "PACKAGE") "0603")
        (field (name "ALLOCATED") "+")
        (field (name "LCSC#") "C106218")
        (field (name "MANF") "YAGEO")
        (field (name "MANF#") "CC0603KRX7R9BB472")
        (field (name "VOLTAGE") "50V")
      )
      (libsource (lib "eagle-import") (part "C-0603"))
    )
    (comp (ref "CON1")
      (value "PINHEAD_1X12-2.54-FEMALE")
      (footprint "eagle-import:1X12-PTH-2.54-FEMALE")
      (libsource (lib "eagle-import") (part "PINHEAD_1X12-2.54-FEMALE"))
    )
    (comp (ref "CON2")
      (value "PINHEAD_1X06-2.54-FEMALE")
      (footprint "eagle-import:1X06-PTH-2.54-FEMALE")
      (libsource (lib "eagle-import") (part "PINHEAD_1X06-2.54-FEMALE"))
    )
    (comp (ref "CON3")
      (value "PINHEAD_1X02-2.54-FEMALE")
      (footprint "eagle-import:1X02-PTH-2.54-FEMALE")
      (libsource (lib "eagle-import") (part "PINHEAD_1X02-2.54-FEMALE"))
    )
    (comp (ref "CON4")
      (value "PINHEAD_1X06-2.54-FEMALE")
      (footprint "eagle-import:1X06-PTH-2.54-FEMALE")
      (libsource (lib "eagle-import") (part "PINHEAD_1X06-2.54-FEMALE"))
    )
    (comp (ref "CON7")
      (value "PINHEAD_1X06-2.54-FEMALE")
      (footprint "eagle-import:1X06-PTH-2.54-FEMALE")
      (libsource (lib "eagle-import") (part "PINHEAD_1X06-2.54-FEMALE"))
    )
    (comp (ref "D1")
      (value "B560C")
      (footprint "eagle-import:DO-214AB(SMC)")
      (fields (field (name "MANF#") "B560C-13-F") (field (name "MANF") "Diodes Incorporated"))
      (libsource (lib "eagle-import") (part "B560C"))
    )
    (comp (ref "D2")
      (value "B560C")
      (footprint "eagle-import:DO-214AB(SMC)")
      (fields (field (name "MANF#") "B560C-13-F") (field (name "MANF") "Diodes Incorporated"))
      (libsource (lib "eagle-import") (part "B560C"))
    )
    (comp (ref "D3")
      (value "B560C")
      (footprint "eagle-import:DO-214AB(SMC)")
      (fields (field (name "MANF#") "B560C-13-F") (field (name "MANF") "Diodes Incorporated"))
      (libsource (lib "eagle-import") (part "B560C"))
    )
    (comp (ref "D4")
      (value "B560C")
      (footprint "eagle-import:DO-214AB(SMC)")
      (fields (field (name "MANF#") "B560C-13-F") (field (name "MANF") "Diodes Incorporated"))
      (libsource (lib "eagle-import") (part "B560C"))
    )
    (comp (ref "D10")
      (value "B560C")
      (footprint "eagle-import:DO-214AB(SMC)")
      (fields (field (name "MANF#") "B560C-13-F") (field (name "MANF") "Diodes Incorporated"))
      (libsource (lib "eagle-import") (part "B560C"))
    )
    (comp (ref "IC1")
      (value "TPS54560B")
      (footprint "eagle-import:SOIC8-POWERPAD")
      (fields (field (name "MANF#") "TPS54560BQDDARQ1") (field (name "MANF") "Texas Instruments"))
      (libsource (lib "eagle-import") (part "TPS54560B"))
    )
    (comp (ref "IC2")
      (value "TPS54560B")
      (footprint "eagle-import:SOIC8-POWERPAD")
      (fields (field (name "MANF#") "TPS54560BQDDARQ1") (field (name "MANF") "Texas Instruments"))
      (libsource (lib "eagle-import") (part "TPS54560B"))
    )
    (comp (ref "IC3")
      (value "TPS54560B")
      (footprint "eagle-import:SOIC8-POWERPAD")
      (fields (field (name "MANF#") "TPS54560BQDDARQ1") (field (name "MANF") "Texas Instruments"))
      (libsource (lib "eagle-import") (part "TPS54560B"))
    )
    (comp (ref "IC4")
      (value "TPS54560B")
      (footprint "eagle-import:SOIC8-POWERPAD")
      (fields (field (name "MANF#") "TPS54560BQDDARQ1") (field (name "MANF") "Texas Instruments"))
      (libsource (lib "eagle-import") (part "TPS54560B"))
    )
    (comp (ref "IC10")
      (value "TPS54260")
      (footprint "eagle-import:MSOP10")
      (fields
        (field (name "MANF#") "TPS54260DGQR")
        (field (name "MANF") "Texas Instruments")
        (field (name "DIGIKEY#") "296-28183-1-ND")
        (field (name "MANF_1") "Texas Instruments")
        (field (name "MANF#_1") "TPS54260QDGQRQ1")
      )
      (libsource (lib "eagle-import") (part "TPS54260"))
    )
    (comp (ref "J1")
      (value "CONNECTION-7MM")
      (footprint "eagle-import:CONNECTION_7MM")
      (libsource (lib "eagle-import") (part "CONNECTION-7MM"))
    )
    (comp (ref "L1")
      (value "3.3uH")
      (footprint "eagle-import:IHLP-2020BZ-01")
      (fields (field (name "MANF") "Vishay Precision Group"))
      (libsource (lib "eagle-import") (part "3.3µH-IHLP-202BZ"))
    )
    (comp (ref "L2")
      (value "7.2uH")
      (footprint "eagle-import:1064")
      (fields (field (name "MANF") "Wurth Elektronik"))
      (libsource (lib "eagle-import") (part "7.2µH-1064"))
    )
    (comp (ref "L3")
      (value "22µH")
      (footprint "eagle-import:SRP1265A")
      (fields (field (name "MANF") "Bourns"))
      (libsource (lib "eagle-import") (part "22µH-SRP1265A"))
    )
    (comp (ref "L4")
      (value "7.2uH")
      (footprint "eagle-import:1064")
      (fields (field (name "MANF") "Wurth Elektronik"))
      (libsource (lib "eagle-import") (part "7.2µH-1064"))
    )
    (comp (ref "L5")
      (value "7.2uH")
      (footprint "eagle-import:1064")
      (fields (field (name "MANF") "Wurth Elektronik"))
      (libsource (lib "eagle-import") (part "7.2µH-1064"))
    )
    (comp (ref "R1")
      (value "243K")
      (footprint "eagle-import:R0603")
      (fields
        (field (name "PACKAGE") "0603")
        (field (name "TOLERANCE") "1%")
        (field (name "ALLOCATED") "+")
        (field (name "LCSC#") "C23351")
        (field (name "MANF") "UNI-ROYAL(Uniroyal Elec)")
        (field (name "MANF#") "0603WAF2433T5E")
      )
      (libsource (lib "eagle-import") (part "R-0603-1%"))
    )
    (comp (ref "R2")
      (value "18K")
      (footprint "eagle-import:R0603")
      (fields
        (field (name "PACKAGE") "0603")
        (field (name "TOLERANCE") "1%")
        (field (name "ALLOCATED") "+")
        (field (name "LCSC#") "C25810")
        (field (name "MANF") "UNI-ROYAL")
        (field (name "MANF#") "0603WAF1802T5E")
      )
      (libsource (lib "eagle-import") (part "R-0603-1%"))
    )
    (comp (ref "R3")
      (value "53K6")
      (footprint "eagle-import:R0603")
      (fields
        (field (name "PACKAGE") "0603")
        (field (name "TOLERANCE") "1%")
        (field (name "ALLOCATED") "+")
        (field (name "LCSC#") "C23074")
        (field (name "MANF") "UNI-ROYAL(Uniroyal Elec)")
        (field (name "MANF#") "0603WAF5362T5E")
      )
      (libsource (lib "eagle-import") (part "R-0603-1%"))
    )
    (comp (ref "R4")
      (value "10K")
      (footprint "eagle-import:R0603")
      (fields
        (field (name "PACKAGE") "0603")
        (field (name "TOLERANCE") "1%")
        (field (name "ALLOCATED") "+")
        (field (name "LCSC#") "C160601")
        (field (name "MANF") "YAGEO")
        (field (name "MANF#") "RT0603FRD0710KL")
      )
      (libsource (lib "eagle-import") (part "R-0603-1%"))
    )
    (comp (ref "R5")
      (value "243K")
      (footprint "eagle-import:R0603")
      (fields
        (field (name "PACKAGE") "0603")
        (field (name "TOLERANCE") "1%")
        (field (name "ALLOCATED") "+")
        (field (name "LCSC#") "C23351")
        (field (name "MANF") "UNI-ROYAL(Uniroyal Elec)")
        (field (name "MANF#") "0603WAF2433T5E")
      )
      (libsource (lib "eagle-import") (part "R-0603-1%"))
    )
    (comp (ref "R6")
      (value "18K")
      (footprint "eagle-import:R0603")
      (fields
        (field (name "PACKAGE") "0603")
        (field (name "TOLERANCE") "1%")
        (field (name "ALLOCATED") "+")
        (field (name "LCSC#") "C25810")
        (field (name "MANF") "UNI-ROYAL")
        (field (name "MANF#") "0603WAF1802T5E")
      )
      (libsource (lib "eagle-import") (part "R-0603-1%"))
    )
    (comp (ref "R7")
      (value "143K")
      (footprint "eagle-import:R0603")
      (fields
        (field (name "PACKAGE") "0603")
        (field (name "TOLERANCE") "1%")
        (field (name "ALLOCATED") "+")
        (field (name "LCSC#") "C22877")
        (field (name "MANF") "UNI-ROYAL(Uniroyal Elec)")
        (field (name "MANF#") "0603WAF1433T5E")
      )
      (libsource (lib "eagle-import") (part "R-0603-1%"))
    )
    (comp (ref "R8")
      (value "10K")
      (footprint "eagle-import:R0603")
      (fields
        (field (name "PACKAGE") "0603")
        (field (name "TOLERANCE") "1%")
        (field (name "ALLOCATED") "+")
        (field (name "LCSC#") "C160601")
        (field (name "MANF") "YAGEO")
        (field (name "MANF#") "RT0603FRD0710KL")
      )
      (libsource (lib "eagle-import") (part "R-0603-1%"))
    )
    (comp (ref "R9")
      (value "243K")
      (footprint "eagle-import:R0603")
      (fields
        (field (name "PACKAGE") "0603")
        (field (name "TOLERANCE") "1%")
        (field (name "ALLOCATED") "+")
        (field (name "LCSC#") "C23351")
        (field (name "MANF") "UNI-ROYAL(Uniroyal Elec)")
        (field (name "MANF#") "0603WAF2433T5E")
      )
      (libsource (lib "eagle-import") (part "R-0603-1%"))
    )
    (comp (ref "R10")
      (value "18K")
      (footprint "eagle-import:R0603")
      (fields
        (field (name "PACKAGE") "0603")
        (field (name "TOLERANCE") "1%")
        (field (name "ALLOCATED") "+")
        (field (name "LCSC#") "C25810")
        (field (name "MANF") "UNI-ROYAL")
        (field (name "MANF#") "0603WAF1802T5E")
      )
      (libsource (lib "eagle-import") (part "R-0603-1%"))
    )
    (comp (ref "R11")
      (value "53K6")
      (footprint "eagle-import:R0603")
      (fields
        (field (name "PACKAGE") "0603")
        (field (name "TOLERANCE") "1%")
        (field (name "ALLOCATED") "+")
        (field (name "LCSC#") "C23074")
        (field (name "MANF") "UNI-ROYAL(Uniroyal Elec)")
        (field (name "MANF#") "0603WAF5362T5E")
      )
      (libsource (lib "eagle-import") (part "R-0603-1%"))
    )
    (comp (ref "R12")
      (value "10K")
      (footprint "eagle-import:R0603")
      (fields
        (field (name "PACKAGE") "0603")
        (field (name "TOLERANCE") "1%")
        (field (name "ALLOCATED") "+")
        (field (name "LCSC#") "C160601")
        (field (name "MANF") "YAGEO")
        (field (name "MANF#") "RT0603FRD0710KL")
      )
      (libsource (lib "eagle-import") (part "R-0603-1%"))
    )
    (comp (ref "R13")
      (value "243K")
      (footprint "eagle-import:R0603")
      (fields
        (field (name "PACKAGE") "0603")
        (field (name "TOLERANCE") "1%")
        (field (name "ALLOCATED") "+")
        (field (name "LCSC#") "C23351")
        (field (name "MANF") "UNI-ROYAL(Uniroyal Elec)")
        (field (name "MANF#") "0603WAF2433T5E")
      )
      (libsource (lib "eagle-import") (part "R-0603-1%"))
    )
    (comp (ref "R14")
      (value "18K")
      (footprint "eagle-import:R0603")
      (fields
        (field (name "PACKAGE") "0603")
        (field (name "TOLERANCE") "1%")
        (field (name "ALLOCATED") "+")
        (field (name "LCSC#") "C25810")
        (field (name "MANF") "UNI-ROYAL")
        (field (name "MANF#") "0603WAF1802T5E")
      )
      (libsource (lib "eagle-import") (part "R-0603-1%"))
    )
    (comp (ref "R15")
      (value "143K")
      (footprint "eagle-import:R0603")
      (fields
        (field (name "PACKAGE") "0603")
        (field (name "TOLERANCE") "1%")
        (field (name "ALLOCATED") "+")
        (field (name "LCSC#") "C23074")
        (field (name "MANF") "UNI-ROYAL(Uniroyal Elec)")
        (field (name "MANF#") "0603WAF5362T5E")
      )
      (libsource (lib "eagle-import") (part "R-0603-1%"))
    )
    (comp (ref "R16")
      (value "10K")
      (footprint "eagle-import:R0603")
      (fields
        (field (name "PACKAGE") "0603")
        (field (name "TOLERANCE") "1%")
        (field (name "ALLOCATED") "+")
        (field (name "LCSC#") "C160601")
        (field (name "MANF") "YAGEO")
        (field (name "MANF#") "RT0603FRD0710KL")
      )
      (libsource (lib "eagle-import") (part "R-0603-1%"))
    )
    (comp (ref "R17")
      (value "10K")
      (footprint "eagle-import:R0603")
      (fields
        (field (name "PACKAGE") "0603")
        (field (name "TOLERANCE") "1%")
        (field (name "ALLOCATED") "+")
        (field (name "LCSC#") "C160601")
        (field (name "MANF") "YAGEO")
        (field (name "MANF#") "RT0603FRD0710KL")
      )
      (libsource (lib "eagle-import") (part "R-0603-1%"))
    )
    (comp (ref "R25")
      (value "143K")
      (footprint "eagle-import:R0603")
      (fields
        (field (name "PACKAGE") "0603")
        (field (name "TOLERANCE") "1%")
        (field (name "ALLOCATED") "+")
        (field (name "LCSC#") "C22877")
        (field (name "MANF") "UNI-ROYAL(Uniroyal Elec)")
        (field (name "MANF#") "0603WAF1433T5E")
      )
      (libsource (lib "eagle-import") (part "R-0603-1%"))
    )
    (comp (ref "R27")
      (value "143K")
      (footprint "eagle-import:R0603")
      (fields
        (field (name "PACKAGE") "0603")
        (field (name "TOLERANCE") "1%")
        (field (name "ALLOCATED") "+")
        (field (name "LCSC#") "C22877")
        (field (name "MANF") "UNI-ROYAL(Uniroyal Elec)")
        (field (name "MANF#") "0603WAF1433T5E")
      )
      (libsource (lib "eagle-import") (part "R-0603-1%"))
    )
    (comp (ref "R28")
      (value "10K")
      (footprint "eagle-import:R0603")
      (fields
        (field (name "PACKAGE") "0603")
        (field (name "TOLERANCE") "1%")
        (field (name "ALLOCATED") "+")
        (field (name "LCSC#") "C160601")
        (field (name "MANF") "YAGEO")
        (field (name "MANF#") "RT0603FRD0710KL")
      )
      (libsource (lib "eagle-import") (part "R-0603-1%"))
    )
    (comp (ref "R29")
      (value "18K")
      (footprint "eagle-import:R0603")
      (fields
        (field (name "PACKAGE") "0603")
        (field (name "TOLERANCE") "1%")
        (field (name "ALLOCATED") "+")
        (field (name "LCSC#") "C25810")
        (field (name "MANF") "UNI-ROYAL")
        (field (name "MANF#") "0603WAF1802T5E")
      )
      (libsource (lib "eagle-import") (part "R-0603-1%"))
    )
  )
  (nets
    (net (code "1") (name "5V") (class "Default")
      (node (ref "C22") (pin "P$2") (pinfunction "2_P$2") (pintype "passive"))
      (node (ref "C23") (pin "P$2") (pinfunction "2_P$2") (pintype "passive"))
      (node (ref "C24") (pin "P$2") (pinfunction "2_P$2") (pintype "passive"))
      (node (ref "CON4") (pin "1") (pinfunction "1_1") (pintype "passive"))
      (node (ref "CON4") (pin "2") (pinfunction "2_2") (pintype "passive"))
      (node (ref "CON4") (pin "3") (pinfunction "3_3") (pintype "passive"))
      (node (ref "L4") (pin "2") (pinfunction "2_2") (pintype "bidirectional"))
      (node (ref "R11") (pin "2") (pinfunction "2_2") (pintype "passive"))
    )
    (net (code "2") (name "5VFMU") (class "Default")
      (node (ref "C39") (pin "2") (pinfunction "2_2") (pintype "passive"))
      (node (ref "C7") (pin "P$2") (pinfunction "2_P$2") (pintype "passive"))
      (node (ref "C8") (pin "P$2") (pinfunction "2_P$2") (pintype "passive"))
      (node (ref "C9") (pin "P$2") (pinfunction "2_P$2") (pintype "passive"))
      (node (ref "CON1") (pin "10") (pinfunction "10_10") (pintype "passive"))
      (node (ref "CON1") (pin "8") (pinfunction "8_8") (pintype "passive"))
      (node (ref "CON1") (pin "9") (pinfunction "9_9") (pintype "passive"))
      (node (ref "IC5") (pin "5") (pinfunction "V+_5") (pintype "bidirectional"))
      (node (ref "L2") (pin "2") (pinfunction "2_2") (pintype "bidirectional"))
      (node (ref "R3") (pin "2") (pinfunction "2_2") (pintype "passive"))
    )
    (net (code "3") (name "12V") (class "Default")
      (node (ref "C36") (pin "P$2") (pinfunction "2_P$2") (pintype "passive"))
      (node (ref "C37") (pin "P$2") (pinfunction "2_P$2") (pintype "passive"))
      (node (ref "C38") (pin "P$2") (pinfunction "2_P$2") (pintype "passive"))
      (node (ref "CON7") (pin "1") (pinfunction "1_1") (pintype "passive"))
      (node (ref "CON7") (pin "2") (pinfunction "2_2") (pintype "passive"))
      (node (ref "CON7") (pin "3") (pinfunction "3_3") (pintype "passive"))
      (node (ref "L5") (pin "2") (pinfunction "2_2") (pintype "bidirectional"))
      (node (ref "R15") (pin "2") (pinfunction "2_2") (pintype "passive"))
    )
    (net (code "4") (name "24V") (class "Default")
      (node (ref "C28") (pin "2") (pinfunction "2_2") (pintype "passive"))
      (node (ref "C29") (pin "2") (pinfunction "2_2") (pintype "passive"))
      (node (ref "C30") (pin "2") (pinfunction "2_2") (pintype "passive"))
      (node (ref "C31") (pin "2") (pinfunction "2_2") (pintype "passive"))
      (node (ref "C32") (pin "2") (pinfunction "2_2") (pintype "passive"))
      (node (ref "C42") (pin "2") (pinfunction "2_2") (pintype "passive"))
      (node (ref "CON2") (pin "4") (pinfunction "4_4") (pintype "passive"))
      (node (ref "CON2") (pin "5") (pinfunction "5_5") (pintype "passive"))
      (node (ref "CON2") (pin "6") (pinfunction "6_6") (pintype "passive"))
      (node (ref "L3") (pin "2") (pinfunction "2_2") (pintype "bidirectional"))
      (node (ref "R7") (pin "2") (pinfunction "2_2") (pintype "passive"))
    )
    (net (code "5") (name "B1MID") (class "Default")
      (node (ref "B1H") (pin "-") (pinfunction "-_-") (pintype "bidirectional"))
      (node (ref "B1L") (pin "+") (pinfunction "+_+") (pintype "bidirectional"))
      (node (ref "PAD4") (pin "P$1") (pinfunction "P$1_P$1") (pintype "bidirectional"))
      (node (ref "PAD8") (pin "P$1") (pinfunction "P$1_P$1") (pintype "bidirectional"))
      (node (ref "R33") (pin "2") (pinfunction "2_2") (pintype "passive"))
    )
    (net (code "6") (name "B2MID") (class "Default")
      (node (ref "B3H") (pin "-") (pinfunction "-_-") (pintype "bidirectional"))
      (node (ref "B3L") (pin "+") (pinfunction "+_+") (pintype "bidirectional"))
      (node (ref "PAD1") (pin "P$1") (pinfunction "P$1_P$1") (pintype "bidirectional"))
      (node (ref "PAD2") (pin "P$1") (pinfunction "P$1_P$1") (pintype "bidirectional"))
      (node (ref "R37") (pin "2") (pinfunction "2_2") (pintype "passive"))
    )
    (net (code "7") (name "B3MID") (class "Default")
      (node (ref "B2H") (pin "-") (pinfunction "-_-") (pintype "bidirectional"))
      (node (ref "B2L") (pin "+") (pinfunction "+_+") (pintype "bidirectional"))
      (node (ref "PAD3") (pin "P$1") (pinfunction "P$1_P$1") (pintype "bidirectional"))
      (node (ref "PAD5") (pin "P$1") (pinfunction "P$1_P$1") (pintype "bidirectional"))
      (node (ref "R44") (pin "2") (pinfunction "2_2") (pintype "passive"))
    )
    (net (code "8") (name "BAT1_MID_V") (class "Default")
      (node (ref "R30") (pin "2") (pinfunction "2_2") (pintype "passive"))
      (node (ref "R33") (pin "1") (pinfunction "1_1") (pintype "passive"))
    )
    (net (code "9") (name "BAT1_ON") (class "Default")
      (node (ref "Q6") (pin "1") (pinfunction "G_1") (pintype "passive"))
      (node (ref "R26") (pin "2") (pinfunction "2_2") (pintype "passive"))
    )
    (net (code "10") (name "BAT1_V") (class "Default")
      (node (ref "R31") (pin "2") (pinfunction "2_2") (pintype "passive"))
      (node (ref "R32") (pin "1") (pinfunction "1_1") (pintype "passive"))
    )
    (net (code "11") (name "BAT2_MID_V") (class "Default")
      (node (ref "R36") (pin "2") (pinfunction "2_2") (pintype "passive"))
      (node (ref "R37") (pin "1") (pinfunction "1_1") (pintype "passive"))
    )
    (net (code "12") (name "BAT2_ON") (class "Default")
      (node (ref "Q2") (pin "1") (pinfunction "G_1") (pintype "passive"))
      (node (ref "R40") (pin "2") (pinfunction "2_2") (pintype "passive"))
    )
    (net (code "13") (name "BAT2_V") (class "Default")
      (node (ref "R34") (pin "2") (pinfunction "2_2") (pintype "passive"))
      (node (ref "R35") (pin "1") (pinfunction "1_1") (pintype "passive"))
    )
    (net (code "14") (name "BAT3_MID_V") (class "Default")
      (node (ref "R43") (pin "2") (pinfunction "2_2") (pintype "passive"))
      (node (ref "R44") (pin "1") (pinfunction "1_1") (pintype "passive"))
    )
    (net (code "15") (name "BAT3_ON") (class "Default")
      (node (ref "Q8") (pin "1") (pinfunction "G_1") (pintype "passive"))
      (node (ref "R47") (pin "2") (pinfunction "2_2") (pintype "passive"))
    )
    (net (code "16") (name "BAT3_V") (class "Default")
      (node (ref "R41") (pin "2") (pinfunction "2_2") (pintype "passive"))
      (node (ref "R42") (pin "1") (pinfunction "1_1") (pintype "passive"))
    )
    (net (code "17") (name "BATNEG") (class "Default")
      (node (ref "B1L") (pin "-") (pinfunction "-_-") (pintype "bidirectional"))
      (node (ref "B2L") (pin "-") (pinfunction "-_-") (pintype "bidirectional"))
      (node (ref "B3L") (pin "-") (pinfunction "-_-") (pintype "bidirectional"))
      (node (ref "CON3") (pin "1") (pinfunction "1_1") (pintype "passive"))
      (node (ref "M1") (pin "-") (pinfunction "-_-") (pintype "bidirectional"))
      (node (ref "M2") (pin "-") (pinfunction "-_-") (pintype "bidirectional"))
      (node (ref "M3") (pin "-") (pinfunction "-_-") (pintype "bidirectional"))
      (node (ref "M4") (pin "-") (pinfunction "-_-") (pintype "bidirectional"))
      (node (ref "M5") (pin "-") (pinfunction "-_-") (pintype "bidirectional"))
      (node (ref "M6") (pin "-") (pinfunction "-_-") (pintype "bidirectional"))
      (node (ref "PLPWR") (pin "-") (pinfunction "-_-") (pintype "bidirectional"))
      (node (ref "Q2") (pin "2") (pinfunction "S_2") (pintype "passive"))
      (node (ref "Q6") (pin "2") (pinfunction "S_2") (pintype "passive"))
      (node (ref "Q8") (pin "2") (pinfunction "S_2") (pintype "passive"))
      (node (ref "R26") (pin "1") (pinfunction "1_1") (pintype "passive"))
      (node (ref "R30") (pin "1") (pinfunction "1_1") (pintype "passive"))
      (node (ref "R31") (pin "1") (pinfunction "1_1") (pintype "passive"))
      (node (ref "R34") (pin "1") (pinfunction "1_1") (pintype "passive"))
      (node (ref "R36") (pin "1") (pinfunction "1_1") (pintype "passive"))
      (node (ref "R40") (pin "1") (pinfunction "1_1") (pintype "passive"))
      (node (ref "R41") (pin "1") (pinfunction "1_1") (pintype "passive"))
      (node (ref "R43") (pin "1") (pinfunction "1_1") (pintype "passive"))
      (node (ref "R47") (pin "1") (pinfunction "1_1") (pintype "passive"))
      (node (ref "SW1") (pin "1") (pinfunction "1_1") (pintype "bidirectional"))
    )
    (net (code "18") (name "BATT_CURRENT") (class "Default")
      (node (ref "C40") (pin "2") (pinfunction "2_2") (pintype "passive"))
      (node (ref "CON1") (pin "12") (pinfunction "12_12") (pintype "passive"))
      (node (ref "IC5") (pin "1") (pinfunction "OUT_1") (pintype "bidirectional"))
      (node (ref "R19") (pin "2") (pinfunction "2_2") (pintype "passive"))
    )
    (net (code "19") (name "BATT_VOLTAGE") (class "Default")
      (node (ref "C41") (pin "2") (pinfunction "2_2") (pintype "passive"))
      (node (ref "CON1") (pin "11") (pinfunction "11_11") (pintype "passive"))
      (node (ref "R20") (pin "2") (pinfunction "2_2") (pintype "passive"))
      (node (ref "R22") (pin "1") (pinfunction "1_1") (pintype "passive"))
    )
    (net (code "20") (name "GND") (class "Default")
      (node (ref "C11") (pin "P$1") (pinfunction "1_P$1") (pintype "passive"))
      (node (ref "C12") (pin "P$1") (pinfunction "1_P$1") (pintype "passive"))
      (node (ref "C13") (pin "P$1") (pinfunction "1_P$1") (pintype "passive"))
      (node (ref "C14") (pin "1") (pinfunction "1_1") (pintype "passive"))
      (node (ref "C15") (pin "1") (pinfunction "1_1") (pintype "passive"))
      (node (ref "C17") (pin "P$1") (pinfunction "1_P$1") (pintype "passive"))
      (node (ref "C18") (pin "P$1") (pinfunction "1_P$1") (pintype "passive"))
      (node (ref "C19") (pin "P$1") (pinfunction "1_P$1") (pintype "passive"))
      (node (ref "C2") (pin "P$1") (pinfunction "1_P$1") (pintype "passive"))
      (node (ref "C20") (pin "1") (pinfunction "1_1") (pintype "passive"))
      (node (ref "C21") (pin "1") (pinfunction "1_1") (pintype "passive"))
      (node (ref "C22") (pin "P$1") (pinfunction "1_P$1") (pintype "passive"))
      (node (ref "C23") (pin "P$1") (pinfunction "1_P$1") (pintype "passive"))
      (node (ref "C24") (pin "P$1") (pinfunction "1_P$1") (pintype "passive"))
      (node (ref "C26") (pin "P$1") (pinfunction "1_P$1") (pintype "passive"))
      (node (ref "C27") (pin "P$1") (pinfunction "1_P$1") (pintype "passive"))
      (node (ref "C28") (pin "1") (pinfunction "1_1") (pintype "passive"))
      (node (ref "C29") (pin "1") (pinfunction "1_1") (pintype "passive"))
      (node (ref "C3") (pin "P$1") (pinfunction "1_P$1") (pintype "passive"))
      (node (ref "C30") (pin "1") (pinfunction "1_1") (pintype "passive"))
      (node (ref "C31") (pin "1") (pinfunction "1_1") (pintype "passive"))
      (node (ref "C32") (pin "1") (pinfunction "1_1") (pintype "passive"))
      (node (ref "C33") (pin "P$1") (pinfunction "1_P$1") (pintype "passive"))
      (node (ref "C34") (pin "1") (pinfunction "1_1") (pintype "passive"))
      (node (ref "C35") (pin "1") (pinfunction "1_1") (pintype "passive"))
      (node (ref "C36") (pin "P$1") (pinfunction "1_P$1") (pintype "passive"))
      (node (ref "C37") (pin "P$1") (pinfunction "1_P$1") (pintype "passive"))
      (node (ref "C38") (pin "P$1") (pinfunction "1_P$1") (pintype "passive"))
      (node (ref "C39") (pin "1") (pinfunction "1_1") (pintype "passive"))
      (node (ref "C4") (pin "P$1") (pinfunction "1_P$1") (pintype "passive"))
      (node (ref "C40") (pin "1") (pinfunction "1_1") (pintype "passive"))
      (node (ref "C41") (pin "1") (pinfunction "1_1") (pintype "passive"))
      (node (ref "C42") (pin "1") (pinfunction "1_1") (pintype "passive"))
      (node (ref "C43") (pin "P$2") (pinfunction "2_P$2") (pintype "passive"))
      (node (ref "C44") (pin "P$1") (pinfunction "1_P$1") (pintype "passive"))
      (node (ref "C5") (pin "1") (pinfunction "1_1") (pintype "passive"))
      (node (ref "C54") (pin "P$1") (pinfunction "1_P$1") (pintype "passive"))
      (node (ref "C56") (pin "P$2") (pinfunction "2_P$2") (pintype "passive"))
      (node (ref "C57") (pin "P$2") (pinfunction "2_P$2") (pintype "passive"))
      (node (ref "C6") (pin "1") (pinfunction "1_1") (pintype "passive"))
      (node (ref "C62") (pin "2") (pinfunction "2_2") (pintype "passive"))
      (node (ref "C7") (pin "P$1") (pinfunction "1_P$1") (pintype "passive"))
      (node (ref "C8") (pin "P$1") (pinfunction "1_P$1") (pintype "passive"))
      (node (ref "C87") (pin "2") (pinfunction "2_2") (pintype "passive"))
      (node (ref "C88") (pin "2") (pinfunction "2_2") (pintype "passive"))
      (node (ref "C9") (pin "P$1") (pinfunction "1_P$1") (pintype "passive"))
      (node (ref "CON1") (pin "1") (pinfunction "1_1") (pintype "passive"))
      (node (ref "CON1") (pin "2") (pinfunction "2_2") (pintype "passive"))
      (node (ref "CON1") (pin "5") (pinfunction "5_5") (pintype "passive"))
      (node (ref "CON1") (pin "6") (pinfunction "6_6") (pintype "passive"))
      (node (ref "CON1") (pin "7") (pinfunction "7_7") (pintype "passive"))
      (node (ref "CON2") (pin "1") (pinfunction "1_1") (pintype "passive"))
      (node (ref "CON2") (pin "2") (pinfunction "2_2") (pintype "passive"))
      (node (ref "CON2") (pin "3") (pinfunction "3_3") (pintype "passive"))
      (node (ref "CON4") (pin "4") (pinfunction "4_4") (pintype "passive"))
      (node (ref "CON4") (pin "5") (pinfunction "5_5") (pintype "passive"))
      (node (ref "CON4") (pin "6") (pinfunction "6_6") (pintype "passive"))
      (node (ref "CON7") (pin "4") (pinfunction "4_4") (pintype "passive"))
      (node (ref "CON7") (pin "5") (pinfunction "5_5") (pintype "passive"))
      (node (ref "CON7") (pin "6") (pinfunction "6_6") (pintype "passive"))
      (node (ref "D1") (pin "A") (pinfunction "A_A") (pintype "passive"))
      (node (ref "D10") (pin "A") (pinfunction "A_A") (pintype "passive"))
      (node (ref "D2") (pin "A") (pinfunction "A_A") (pintype "passive"))
      (node (ref "D3") (pin "A") (pinfunction "A_A") (pintype "passive"))
      (node (ref "D4") (pin "A") (pinfunction "A_A") (pintype "passive"))
      (node (ref "IC1") (pin "7") (pinfunction "GND_7") (pintype "bidirectional"))
      (node (ref "IC1") (pin "P$1") (pinfunction "GND_P$1") (pintype "bidirectional"))
      (node (ref "IC10") (pin "9") (pinfunction "GND_9") (pintype "bidirectional"))
      (node (ref "IC10") (pin "EP") (pinfunction "GND_EP") (pintype "bidirectional"))
      (node (ref "IC2") (pin "7") (pinfunction "GND_7") (pintype "bidirectional"))
      (node (ref "IC2") (pin "P$1") (pinfunction "GND_P$1") (pintype "bidirectional"))
      (node (ref "IC3") (pin "7") (pinfunction "GND_7") (pintype "bidirectional"))
      (node (ref "IC3") (pin "P$1") (pinfunction "GND_P$1") (pintype "bidirectional"))
      (node (ref "IC4") (pin "7") (pinfunction "GND_7") (pintype "bidirectional"))
      (node (ref "IC4") (pin "P$1") (pinfunction "GND_P$1") (pintype "bidirectional"))
      (node (ref "IC5") (pin "2") (pinfunction "GND_2") (pintype "bidirectional"))
      (node (ref "J1") (pin "2") (pinfunction "P$2_2") (pintype "bidirectional"))
      (node (ref "R1") (pin "1") (pinfunction "1_1") (pintype "passive"))
      (node (ref "R12") (pin "1") (pinfunction "1_1") (pintype "passive"))
      (node (ref "R13") (pin "1") (pinfunction "1_1") (pintype "passive"))
      (node (ref "R16") (pin "1") (pinfunction "1_1") (pintype "passive"))
      (node (ref "R17") (pin "1") (pinfunction "1_1") (pintype "passive"))
      (node (ref "R19") (pin "1") (pinfunction "1_1") (pintype "passive"))
      (node (ref "R20") (pin "1") (pinfunction "1_1") (pintype "passive"))
      (node (ref "R25") (pin "1") (pinfunction "1_1") (pintype "passive"))
      (node (ref "R28") (pin "1") (pinfunction "1_1") (pintype "passive"))
      (node (ref "R4") (pin "1") (pinfunction "1_1") (pintype "passive"))
      (node (ref "R5") (pin "1") (pinfunction "1_1") (pintype "passive"))
      (node (ref "R8") (pin "1") (pinfunction "1_1") (pintype "passive"))
      (node (ref "R9") (pin "1") (pinfunction "1_1") (pintype "passive"))
    )
    (net (code "21") (name "Net-(C5-Pad2)") (class "Default")
      (node (ref "C5") (pin "2") (pinfunction "2_2") (pintype "passive"))
      (node (ref "R2") (pin "1") (pinfunction "1_1") (pintype "passive"))
    )
    (net (code "22") (name "Net-(C14-Pad2)") (class "Default")
      (node (ref "C14") (pin "2") (pinfunction "2_2") (pintype "passive"))
      (node (ref "R6") (pin "1") (pinfunction "1_1") (pintype "passive"))
    )
    (net (code "23") (name "Net-(C20-Pad2)") (class "Default")
      (node (ref "C20") (pin "2") (pinfunction "2_2") (pintype "passive"))
      (node (ref "R10") (pin "1") (pinfunction "1_1") (pintype "passive"))
    )
    (net (code "24") (name "Net-(C34-Pad2)") (class "Default")
      (node (ref "C34") (pin "2") (pinfunction "2_2") (pintype "passive"))
      (node (ref "R14") (pin "1") (pinfunction "1_1") (pintype "passive"))
    )
    (net (code "25") (name "Net-(C88-Pad1)") (class "Default")
      (node (ref "C88") (pin "1") (pinfunction "1_1") (pintype "passive"))
      (node (ref "R29") (pin "1") (pinfunction "1_1") (pintype "passive"))
    )
    (net (code "26") (name "Net-(IC1-BOOT)") (class "Default")
      (node (ref "C1") (pin "1") (pinfunction "1_1") (pintype "passive"))
      (node (ref "IC1") (pin "1") (pinfunction "BOOT_1") (pintype "bidirectional"))
    )
    (net (code "27") (name "Net-(IC1-COMP)") (class "Default")
      (node (ref "C6") (pin "2") (pinfunction "2_2") (pintype "passive"))
      (node (ref "IC1") (pin "6") (pinfunction "COMP_6") (pintype "bidirectional"))
      (node (ref "R2") (pin "2") (pinfunction "2_2") (pintype "passive"))
    )
    (net (code "28") (name "Net-(IC1-FB)") (class "Default")
      (node (ref "IC1") (pin "5") (pinfunction "FB_5") (pintype "bidirectional"))
      (node (ref "R3") (pin "1") (pinfunction "1_1") (pintype "passive"))
      (node (ref "R4") (pin "2") (pinfunction "2_2") (pintype "passive"))
    )
    (net (code "29") (name "Net-(IC1-RT{slash}CLK)") (class "Default")
      (node (ref "IC1") (pin "4") (pinfunction "RT/CLK_4") (pintype "bidirectional"))
      (node (ref "R1") (pin "2") (pinfunction "2_2") (pintype "passive"))
    )
    (net (code "30") (name "Net-(IC1-SW)") (class "Default")
      (node (ref "C1") (pin "2") (pinfunction "2_2") (pintype "passive"))
      (node (ref "D1") (pin "C") (pinfunction "C_C") (pintype "passive"))
      (node (ref "IC1") (pin "8") (pinfunction "SW_8") (pintype "bidirectional"))
      (node (ref "L2") (pin "1") (pinfunction "1_1") (pintype "bidirectional"))
    )
    (net (code "31") (name "Net-(IC2-BOOT)") (class "Default")
      (node (ref "C10") (pin "1") (pinfunction "1_1") (pintype "passive"))
      (node (ref "IC2") (pin "1") (pinfunction "BOOT_1") (pintype "bidirectional"))
    )
    (net (code "32") (name "Net-(IC2-COMP)") (class "Default")
      (node (ref "C15") (pin "2") (pinfunction "2_2") (pintype "passive"))
      (node (ref "IC2") (pin "6") (pinfunction "COMP_6") (pintype "bidirectional"))
      (node (ref "R6") (pin "2") (pinfunction "2_2") (pintype "passive"))
    )
    (net (code "33") (name "Net-(IC2-FB)") (class "Default")
      (node (ref "IC2") (pin "5") (pinfunction "FB_5") (pintype "bidirectional"))
      (node (ref "R17") (pin "2") (pinfunction "2_2") (pintype "passive"))
      (node (ref "R7") (pin "1") (pinfunction "1_1") (pintype "passive"))
      (node (ref "R8") (pin "2") (pinfunction "2_2") (pintype "passive"))
    )
    (net (code "34") (name "Net-(IC2-RT{slash}CLK)") (class "Default")
      (node (ref "IC2") (pin "4") (pinfunction "RT/CLK_4") (pintype "bidirectional"))
      (node (ref "R5") (pin "2") (pinfunction "2_2") (pintype "passive"))
    )
    (net (code "35") (name "Net-(IC2-SW)") (class "Default")
      (node (ref "C10") (pin "2") (pinfunction "2_2") (pintype "passive"))
      (node (ref "D2") (pin "C") (pinfunction "C_C") (pintype "passive"))
      (node (ref "IC2") (pin "8") (pinfunction "SW_8") (pintype "bidirectional"))
      (node (ref "L3") (pin "1") (pinfunction "1_1") (pintype "bidirectional"))
    )
    (net (code "36") (name "Net-(IC3-BOOT)") (class "Default")
      (node (ref "C16") (pin "1") (pinfunction "1_1") (pintype "passive"))
      (node (ref "IC3") (pin "1") (pinfunction "BOOT_1") (pintype "bidirectional"))
    )
    (net (code "37") (name "Net-(IC3-COMP)") (class "Default")
      (node (ref "C21") (pin "2") (pinfunction "2_2") (pintype "passive"))
      (node (ref "IC3") (pin "6") (pinfunction "COMP_6") (pintype "bidirectional"))
      (node (ref "R10") (pin "2") (pinfunction "2_2") (pintype "passive"))
    )
    (net (code "38") (name "Net-(IC3-FB)") (class "Default")
      (node (ref "IC3") (pin "5") (pinfunction "FB_5") (pintype "bidirectional"))
      (node (ref "R11") (pin "1") (pinfunction "1_1") (pintype "passive"))
      (node (ref "R12") (pin "2") (pinfunction "2_2") (pintype "passive"))
    )
    (net (code "39") (name "Net-(IC3-RT{slash}CLK)") (class "Default")
      (node (ref "IC3") (pin "4") (pinfunction "RT/CLK_4") (pintype "bidirectional"))
      (node (ref "R9") (pin "2") (pinfunction "2_2") (pintype "passive"))
    )
    (net (code "40") (name "Net-(IC3-SW)") (class "Default")
      (node (ref "C16") (pin "2") (pinfunction "2_2") (pintype "passive"))
      (node (ref "D3") (pin "C") (pinfunction "C_C") (pintype "passive"))
      (node (ref "IC3") (pin "8") (pinfunction "SW_8") (pintype "bidirectional"))
      (node (ref "L4") (pin "1") (pinfunction "1_1") (pintype "bidirectional"))
    )
    (net (code "41") (name "Net-(IC4-BOOT)") (class "Default")
      (node (ref "C25") (pin "1") (pinfunction "1_1") (pintype "passive"))
      (node (ref "IC4") (pin "1") (pinfunction "BOOT_1") (pintype "bidirectional"))
    )
    (net (code "42") (name "Net-(IC4-COMP)") (class "Default")
      (node (ref "C35") (pin "2") (pinfunction "2_2") (pintype "passive"))
      (node (ref "IC4") (pin "6") (pinfunction "COMP_6") (pintype "bidirectional"))
      (node (ref "R14") (pin "2") (pinfunction "2_2") (pintype "passive"))
    )
    (net (code "43") (name "Net-(IC4-FB)") (class "Default")
      (node (ref "IC4") (pin "5") (pinfunction "FB_5") (pintype "bidirectional"))
      (node (ref "R15") (pin "1") (pinfunction "1_1") (pintype "passive"))
      (node (ref "R16") (pin "2") (pinfunction "2_2") (pintype "passive"))
    )
    (net (code "44") (name "Net-(IC4-RT{slash}CLK)") (class "Default")
      (node (ref "IC4") (pin "4") (pinfunction "RT/CLK_4") (pintype "bidirectional"))
      (node (ref "R13") (pin "2") (pinfunction "2_2") (pintype "passive"))
    )
    (net (code "45") (name "Net-(IC4-SW)") (class "Default")
      (node (ref "C25") (pin "2") (pinfunction "2_2") (pintype "passive"))
      (node (ref "D4") (pin "C") (pinfunction "C_C") (pintype "passive"))
      (node (ref "IC4") (pin "8") (pinfunction "SW_8") (pintype "bidirectional"))
      (node (ref "L5") (pin "1") (pinfunction "1_1") (pintype "bidirectional"))
    )
    (net (code "46") (name "Net-(IC5-VIN+)") (class "Default")
      (node (ref "IC5") (pin "3") (pinfunction "VIN+_3") (pintype "bidirectional"))
      (node (ref "R18") (pin "S1") (pinfunction "S1_S1") (pintype "bidirectional"))
    )
    (net (code "47") (name "Net-(IC5-VIN-)") (class "Default")
      (node (ref "IC5") (pin "4") (pinfunction "VIN-_4") (pintype "bidirectional"))
      (node (ref "R18") (pin "S2") (pinfunction "S2_S2") (pintype "bidirectional"))
    )
    (net (code "48") (name "Net-(IC10-BOOT)") (class "Default")
      (node (ref "C58") (pin "2") (pinfunction "2_2") (pintype "passive"))
      (node (ref "IC10") (pin "1") (pinfunction "BOOT_1") (pintype "bidirectional"))
    )
    (net (code "49") (name "Net-(IC10-COMP)") (class "Default")
      (node (ref "C87") (pin "1") (pinfunction "1_1") (pintype "passive"))
      (node (ref "IC10") (pin "8") (pinfunction "COMP_8") (pintype "bidirectional"))
      (node (ref "R29") (pin "2") (pinfunction "2_2") (pintype "passive"))
    )
    (net (code "50") (name "Net-(IC10-PH)") (class "Default")
      (node (ref "C58") (pin "1") (pinfunction "1_1") (pintype "passive"))
      (node (ref "D10") (pin "C") (pinfunction "C_C") (pintype "passive"))
      (node (ref "IC10") (pin "10") (pinfunction "PH_10") (pintype "bidirectional"))
      (node (ref "L1") (pin "P$1") (pinfunction "1_P$1") (pintype "bidirectional"))
    )
    (net (code "51") (name "Net-(IC10-RT{slash}CLK)") (class "Default")
      (node (ref "IC10") (pin "5") (pinfunction "RT/CLK_5") (pintype "bidirectional"))
      (node (ref "R25") (pin "2") (pinfunction "2_2") (pintype "passive"))
    )
    (net (code "52") (name "Net-(IC10-SS{slash}TR)") (class "Default")
      (node (ref "C62") (pin "1") (pinfunction "1_1") (pintype "passive"))
      (node (ref "IC10") (pin "4") (pinfunction "SS/TR_4") (pintype "bidirectional"))
    )
    (net (code "53") (name "Net-(IC10-VSENSE)") (class "Default")
      (node (ref "IC10") (pin "7") (pinfunction "VSENSE_7") (pintype "bidirectional"))
      (node (ref "R27") (pin "1") (pinfunction "1_1") (pintype "passive"))
      (node (ref "R28") (pin "2") (pinfunction "2_2") (pintype "passive"))
    )
    (net (code "54") (name "Net-(Q1-G)") (class "Default")
      (node (ref "Q1") (pin "1") (pinfunction "G_1") (pintype "passive"))
      (node (ref "Q2") (pin "3") (pinfunction "D_3") (pintype "passive"))
      (node (ref "Q3") (pin "1") (pinfunction "G_1") (pintype "passive"))
      (node (ref "R39") (pin "1") (pinfunction "1_1") (pintype "passive"))
      (node (ref "ZD2") (pin "A") (pinfunction "A_A") (pintype "passive"))
    )
    (net (code "55") (name "Net-(Q1-S)") (class "Default")
      (node (ref "B3H") (pin "+") (pinfunction "+_+") (pintype "bidirectional"))
      (node (ref "Q1") (pin "3") (pinfunction "S_3") (pintype "passive"))
      (node (ref "Q3") (pin "3") (pinfunction "S_3") (pintype "passive"))
      (node (ref "R38") (pin "2") (pinfunction "2_2") (pintype "passive"))
      (node (ref "R39") (pin "2") (pinfunction "2_2") (pintype "passive"))
      (node (ref "ZD2") (pin "C") (pinfunction "C_C") (pintype "passive"))
    )
    (net (code "56") (name "Net-(Q4-G)") (class "Default")
      (node (ref "Q4") (pin "1") (pinfunction "G_1") (pintype "passive"))
      (node (ref "Q5") (pin "1") (pinfunction "G_1") (pintype "passive"))
      (node (ref "Q6") (pin "3") (pinfunction "D_3") (pintype "passive"))
      (node (ref "R24") (pin "1") (pinfunction "1_1") (pintype "passive"))
      (node (ref "SW1") (pin "2") (pinfunction "2_2") (pintype "bidirectional"))
      (node (ref "ZD1") (pin "A") (pinfunction "A_A") (pintype "passive"))
    )
    (net (code "57") (name "Net-(Q4-S)") (class "Default")
      (node (ref "B1H") (pin "+") (pinfunction "+_+") (pintype "bidirectional"))
      (node (ref "Q4") (pin "3") (pinfunction "S_3") (pintype "passive"))
      (node (ref "Q5") (pin "3") (pinfunction "S_3") (pintype "passive"))
      (node (ref "R23") (pin "2") (pinfunction "2_2") (pintype "passive"))
      (node (ref "R24") (pin "2") (pinfunction "2_2") (pintype "passive"))
      (node (ref "ZD1") (pin "C") (pinfunction "C_C") (pintype "passive"))
    )
    (net (code "58") (name "Net-(Q7-G)") (class "Default")
      (node (ref "Q7") (pin "1") (pinfunction "G_1") (pintype "passive"))
      (node (ref "Q8") (pin "3") (pinfunction "D_3") (pintype "passive"))
      (node (ref "Q9") (pin "1") (pinfunction "G_1") (pintype "passive"))
      (node (ref "R46") (pin "1") (pinfunction "1_1") (pintype "passive"))
      (node (ref "ZD3") (pin "A") (pinfunction "A_A") (pintype "passive"))
    )
    (net (code "59") (name "Net-(Q7-S)") (class "Default")
      (node (ref "B2H") (pin "+") (pinfunction "+_+") (pintype "bidirectional"))
      (node (ref "Q7") (pin "3") (pinfunction "S_3") (pintype "passive"))
      (node (ref "Q9") (pin "3") (pinfunction "S_3") (pintype "passive"))
      (node (ref "R45") (pin "2") (pinfunction "2_2") (pintype "passive"))
      (node (ref "R46") (pin "2") (pinfunction "2_2") (pintype "passive"))
      (node (ref "ZD3") (pin "C") (pinfunction "C_C") (pintype "passive"))
    )
    (net (code "60") (name "Net-(R21-Pad1)") (class "Default")
      (node (ref "R21") (pin "1") (pinfunction "1_1") (pintype "passive"))
      (node (ref "R22") (pin "2") (pinfunction "2_2") (pintype "passive"))
    )
    (net (code "61") (name "Net-(R23-Pad1)") (class "Default")
      (node (ref "R23") (pin "1") (pinfunction "1_1") (pintype "passive"))
      (node (ref "R32") (pin "2") (pinfunction "2_2") (pintype "passive"))
    )
    (net (code "62") (name "Net-(R35-Pad2)") (class "Default")
      (node (ref "R35") (pin "2") (pinfunction "2_2") (pintype "passive"))
      (node (ref "R38") (pin "1") (pinfunction "1_1") (pintype "passive"))
    )
    (net (code "63") (name "Net-(R42-Pad2)") (class "Default")
      (node (ref "R42") (pin "2") (pinfunction "2_2") (pintype "passive"))
      (node (ref "R45") (pin "1") (pinfunction "1_1") (pintype "passive"))
    )
    (net (code "64") (name "PGND") (class "Default")
      (node (ref "J1") (pin "1") (pinfunction "P$1_1") (pintype "bidirectional"))
    )
    (net (code "65") (name "PWRSW") (class "Default")
      (node (ref "CON3") (pin "2") (pinfunction "2_2") (pintype "passive"))
    )
    (net (code "66") (name "VBAT") (class "Default")
      (node (ref "C11") (pin "P$2") (pinfunction "2_P$2") (pintype "passive"))
      (node (ref "C12") (pin "P$2") (pinfunction "2_P$2") (pintype "passive"))
      (node (ref "C13") (pin "P$2") (pinfunction "2_P$2") (pintype "passive"))
      (node (ref "C17") (pin "P$2") (pinfunction "2_P$2") (pintype "passive"))
      (node (ref "C18") (pin "P$2") (pinfunction "2_P$2") (pintype "passive"))
      (node (ref "C19") (pin "P$2") (pinfunction "2_P$2") (pintype "passive"))
      (node (ref "C2") (pin "P$2") (pinfunction "2_P$2") (pintype "passive"))
      (node (ref "C26") (pin "P$2") (pinfunction "2_P$2") (pintype "passive"))
      (node (ref "C27") (pin "P$2") (pinfunction "2_P$2") (pintype "passive"))
      (node (ref "C3") (pin "P$2") (pinfunction "2_P$2") (pintype "passive"))
      (node (ref "C33") (pin "P$2") (pinfunction "2_P$2") (pintype "passive"))
      (node (ref "C4") (pin "P$2") (pinfunction "2_P$2") (pintype "passive"))
      (node (ref "C44") (pin "P$2") (pinfunction "2_P$2") (pintype "passive"))
      (node (ref "C54") (pin "P$2") (pinfunction "2_P$2") (pintype "passive"))
      (node (ref "IC1") (pin "2") (pinfunction "VIN_2") (pintype "bidirectional"))
      (node (ref "IC10") (pin "2") (pinfunction "VIN_2") (pintype "bidirectional"))
      (node (ref "IC2") (pin "2") (pinfunction "VIN_2") (pintype "bidirectional"))
      (node (ref "IC3") (pin "2") (pinfunction "VIN_2") (pintype "bidirectional"))
      (node (ref "IC4") (pin "2") (pinfunction "VIN_2") (pintype "bidirectional"))
      (node (ref "R18") (pin "2") (pinfunction "2_2") (pintype "bidirectional"))
      (node (ref "R18") (pin "22") (pinfunction "2_22") (pintype "bidirectional"))
      (node (ref "R21") (pin "2") (pinfunction "2_2") (pintype "passive"))
    )
    (net (code "67") (name "VDC") (class "Default")
      (node (ref "M1") (pin "+") (pinfunction "+_+") (pintype "bidirectional"))
      (node (ref "M2") (pin "+") (pinfunction "+_+") (pintype "bidirectional"))
      (node (ref "M3") (pin "+") (pinfunction "+_+") (pintype "bidirectional"))
      (node (ref "M4") (pin "+") (pinfunction "+_+") (pintype "bidirectional"))
      (node (ref "M5") (pin "+") (pinfunction "+_+") (pintype "bidirectional"))
      (node (ref "M6") (pin "+") (pinfunction "+_+") (pintype "bidirectional"))
      (node (ref "PLPWR") (pin "+") (pinfunction "+_+") (pintype "bidirectional"))
      (node (ref "Q1") (pin "2") (pinfunction "D_2") (pintype "passive"))
      (node (ref "Q3") (pin "2") (pinfunction "D_2") (pintype "passive"))
      (node (ref "Q4") (pin "2") (pinfunction "D_2") (pintype "passive"))
      (node (ref "Q5") (pin "2") (pinfunction "D_2") (pintype "passive"))
      (node (ref "Q7") (pin "2") (pinfunction "D_2") (pintype "passive"))
      (node (ref "Q9") (pin "2") (pinfunction "D_2") (pintype "passive"))
      (node (ref "R18") (pin "1") (pinfunction "1_1") (pintype "bidirectional"))
      (node (ref "R18") (pin "11") (pinfunction "1_11") (pintype "bidirectional"))
    )
    (net (code "68") (name "VDD_4V") (class "Default")
      (node (ref "C43") (pin "P$1") (pinfunction "1_P$1") (pintype "passive"))
      (node (ref "C56") (pin "P$1") (pinfunction "1_P$1") (pintype "passive"))
      (node (ref "C57") (pin "P$1") (pinfunction "1_P$1") (pintype "passive"))
      (node (ref "CON1") (pin "3") (pinfunction "3_3") (pintype "passive"))
      (node (ref "CON1") (pin "4") (pinfunction "4_4") (pintype "passive"))
      (node (ref "L1") (pin "P$2") (pinfunction "2_P$2") (pintype "bidirectional"))
      (node (ref "R27") (pin "2") (pinfunction "2_2") (pintype "passive"))
    )
    (net (code "69") (name "unconnected-(B1H-PAD1-PadP$3)") (class "Default")
      (node (ref "B1H") (pin "P$3") (pinfunction "PAD1_P$3") (pintype "bidirectional"))
    )
    (net (code "70") (name "unconnected-(B1H-PAD2-PadP$4)") (class "Default")
      (node (ref "B1H") (pin "P$4") (pinfunction "PAD2_P$4") (pintype "bidirectional"))
    )
    (net (code "71") (name "unconnected-(B1L-PAD1-PadP$3)") (class "Default")
      (node (ref "B1L") (pin "P$3") (pinfunction "PAD1_P$3") (pintype "bidirectional"))
    )
    (net (code "72") (name "unconnected-(B1L-PAD2-PadP$4)") (class "Default")
      (node (ref "B1L") (pin "P$4") (pinfunction "PAD2_P$4") (pintype "bidirectional"))
    )
    (net (code "73") (name "unconnected-(B2H-PAD1-PadP$3)") (class "Default")
      (node (ref "B2H") (pin "P$3") (pinfunction "PAD1_P$3") (pintype "bidirectional"))
    )
    (net (code "74") (name "unconnected-(B2H-PAD2-PadP$4)") (class "Default")
      (node (ref "B2H") (pin "P$4") (pinfunction "PAD2_P$4") (pintype "bidirectional"))
    )
    (net (code "75") (name "unconnected-(B2L-PAD1-PadP$3)") (class "Default")
      (node (ref "B2L") (pin "P$3") (pinfunction "PAD1_P$3") (pintype "bidirectional"))
    )
    (net (code "76") (name "unconnected-(B2L-PAD2-PadP$4)") (class "Default")
      (node (ref "B2L") (pin "P$4") (pinfunction "PAD2_P$4") (pintype "bidirectional"))
    )
    (net (code "77") (name "unconnected-(B3H-PAD1-PadP$3)") (class "Default")
      (node (ref "B3H") (pin "P$3") (pinfunction "PAD1_P$3") (pintype "bidirectional"))
    )
    (net (code "78") (name "unconnected-(B3H-PAD2-PadP$4)") (class "Default")
      (node (ref "B3H") (pin "P$4") (pinfunction "PAD2_P$4") (pintype "bidirectional"))
    )
    (net (code "79") (name "unconnected-(B3L-PAD1-PadP$3)") (class "Default")
      (node (ref "B3L") (pin "P$3") (pinfunction "PAD1_P$3") (pintype "bidirectional"))
    )
    (net (code "80") (name "unconnected-(B3L-PAD2-PadP$4)") (class "Default")
      (node (ref "B3L") (pin "P$4") (pinfunction "PAD2_P$4") (pintype "bidirectional"))
    )
    (net (code "81") (name "unconnected-(IC1-EN-Pad3)") (class "Default")
      (node (ref "IC1") (pin "3") (pinfunction "EN_3") (pintype "bidirectional"))
    )
    (net (code "82") (name "unconnected-(IC2-EN-Pad3)") (class "Default")
      (node (ref "IC2") (pin "3") (pinfunction "EN_3") (pintype "bidirectional"))
    )
    (net (code "83") (name "unconnected-(IC3-EN-Pad3)") (class "Default")
      (node (ref "IC3") (pin "3") (pinfunction "EN_3") (pintype "bidirectional"))
    )
    (net (code "84") (name "unconnected-(IC4-EN-Pad3)") (class "Default")
      (node (ref "IC4") (pin "3") (pinfunction "EN_3") (pintype "bidirectional"))
    )
    (net (code "85") (name "unconnected-(IC10-EN-Pad3)") (class "Default")
      (node (ref "IC10") (pin "3") (pinfunction "EN_3") (pintype "bidirectional"))
    )
    (net (code "86") (name "unconnected-(IC10-PWRGD-Pad6)") (class "Default")
      (node (ref "IC10") (pin "6") (pinfunction "PWRGD_6") (pintype "bidirectional"))
    )
    (net (code "87") (name "unconnected-(M1-PAD1-PadP$3)") (class "Default")
      (node (ref "M1") (pin "P$3") (pinfunction "PAD1_P$3") (pintype "bidirectional"))
    )
    (net (code "88") (name "unconnected-(M1-PAD2-PadP$4)") (class "Default")
      (node (ref "M1") (pin "P$4") (pinfunction "PAD2_P$4") (pintype "bidirectional"))
    )
    (net (code "89") (name "unconnected-(M2-PAD1-PadP$3)") (class "Default")
      (node (ref "M2") (pin "P$3") (pinfunction "PAD1_P$3") (pintype "bidirectional"))
    )
    (net (code "90") (name "unconnected-(M2-PAD2-PadP$4)") (class "Default")
      (node (ref "M2") (pin "P$4") (pinfunction "PAD2_P$4") (pintype "bidirectional"))
    )
    (net (code "91") (name "unconnected-(M3-PAD1-PadP$3)") (class "Default")
      (node (ref "M3") (pin "P$3") (pinfunction "PAD1_P$3") (pintype "bidirectional"))
    )
    (net (code "92") (name "unconnected-(M3-PAD2-PadP$4)") (class "Default")
      (node (ref "M3") (pin "P$4") (pinfunction "PAD2_P$4") (pintype "bidirectional"))
    )
    (net (code "93") (name "unconnected-(M4-PAD1-PadP$3)") (class "Default")
      (node (ref "M4") (pin "P$3") (pinfunction "PAD1_P$3") (pintype "bidirectional"))
    )
    (net (code "94") (name "unconnected-(M4-PAD2-PadP$4)") (class "Default")
      (node (ref "M4") (pin "P$4") (pinfunction "PAD2_P$4") (pintype "bidirectional"))
    )
    (net (code "95") (name "unconnected-(M5-PAD1-PadP$3)") (class "Default")
      (node (ref "M5") (pin "P$3") (pinfunction "PAD1_P$3") (pintype "bidirectional"))
    )
    (net (code "96") (name "unconnected-(M5-PAD2-PadP$4)") (class "Default")
      (node (ref "M5") (pin "P$4") (pinfunction "PAD2_P$4") (pintype "bidirectional"))
    )
    (net (code "97") (name "unconnected-(M6-PAD1-PadP$3)") (class "Default")
      (node (ref "M6") (pin "P$3") (pinfunction "PAD1_P$3") (pintype "bidirectional"))
    )
    (net (code "98") (name "unconnected-(M6-PAD2-PadP$4)") (class "Default")
      (node (ref "M6") (pin "P$4") (pinfunction "PAD2_P$4") (pintype "bidirectional"))
    )
    (net (code "99") (name "unconnected-(PLPWR-PAD1-PadP$3)") (class "Default")
      (node (ref "PLPWR") (pin "P$3") (pinfunction "PAD1_P$3") (pintype "bidirectional"))
    )
    (net (code "100") (name "unconnected-(PLPWR-PAD2-PadP$4)") (class "Default")
      (node (ref "PLPWR") (pin "P$4") (pinfunction "PAD2_P$4") (pintype "bidirectional"))
    )
  )
)
